# merge.net
KiCad netlist of a schematic drawn in EAGLE
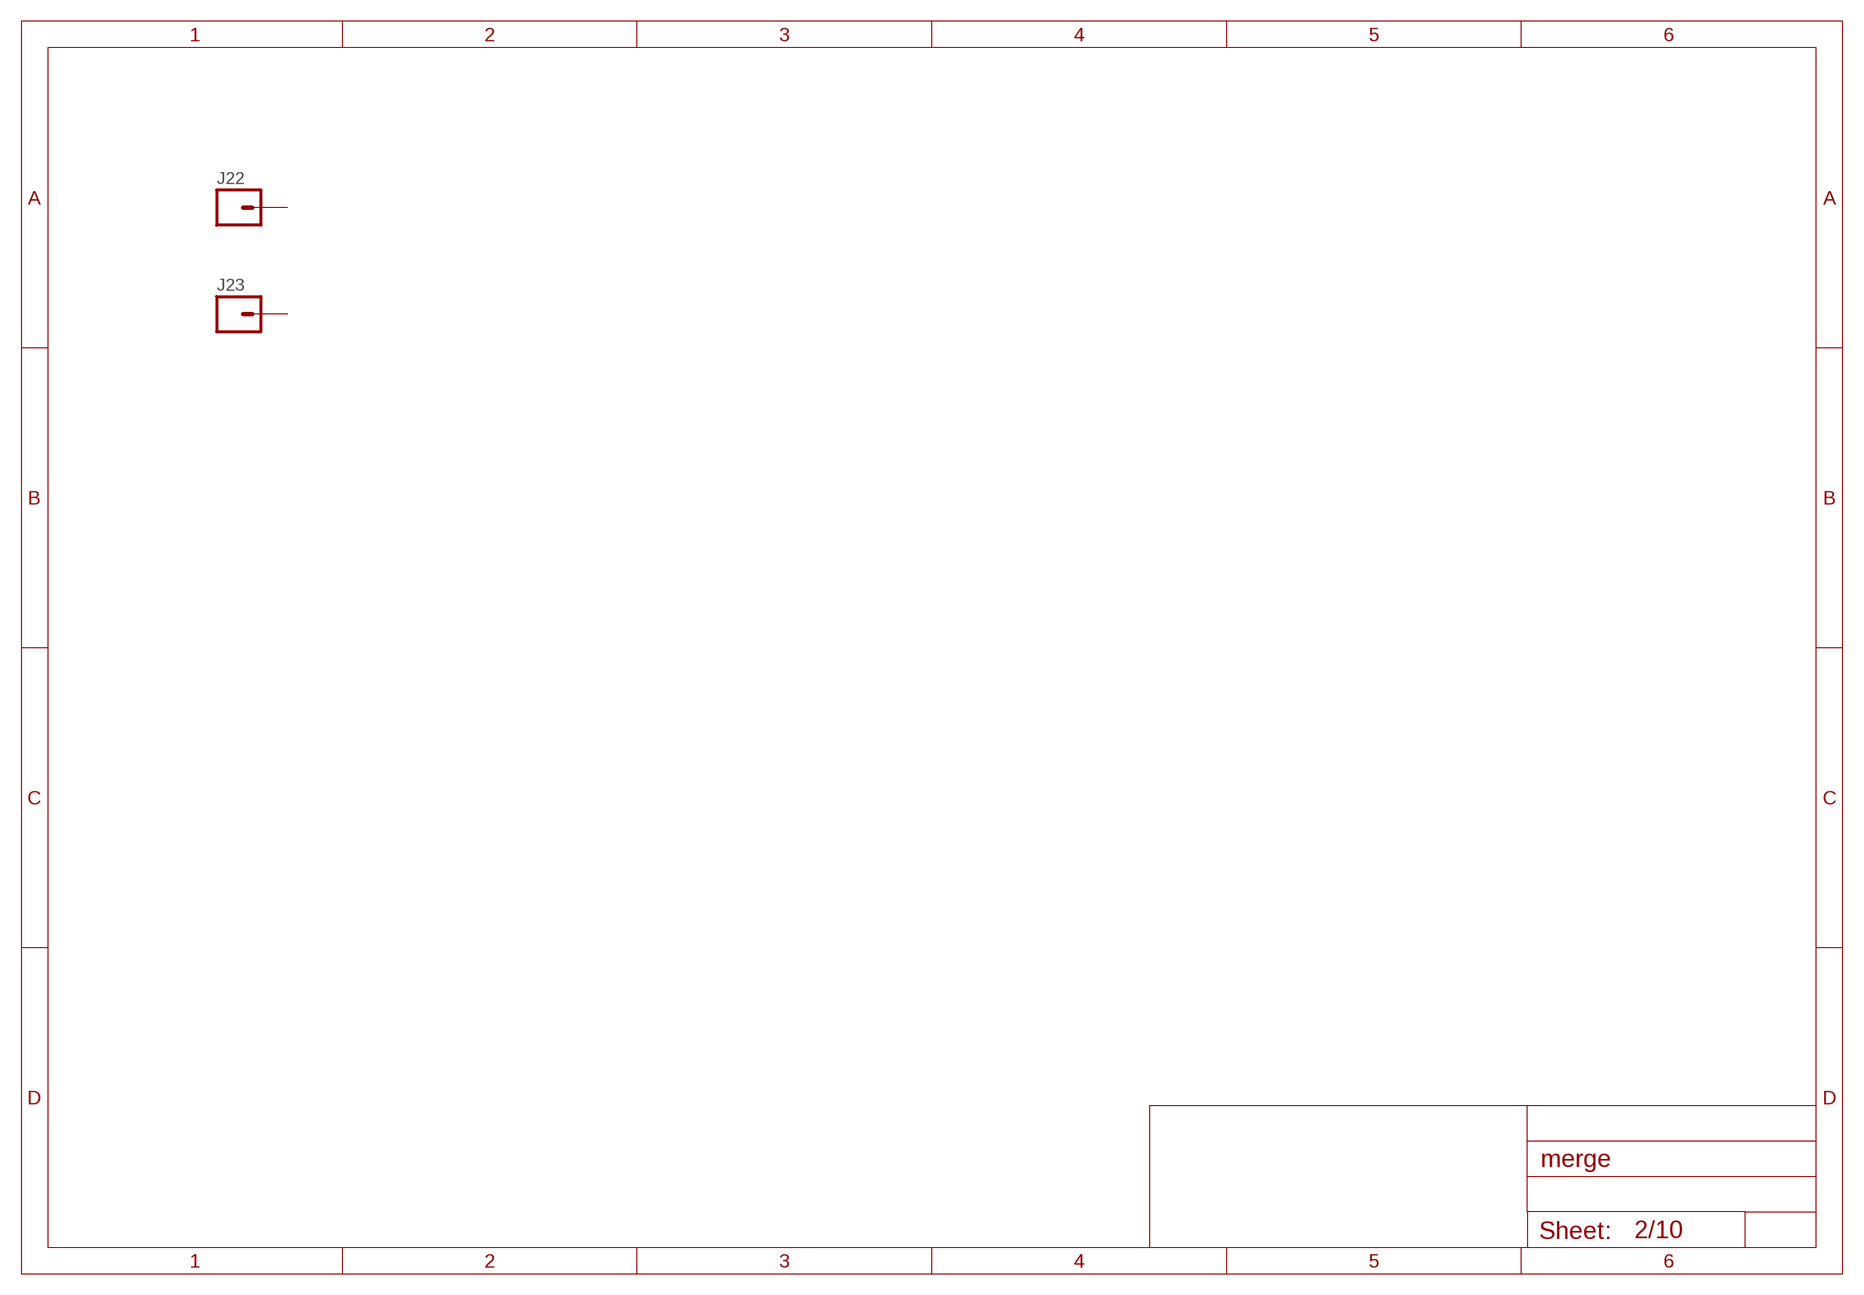
[diagram p0: schematic, sheet 2]
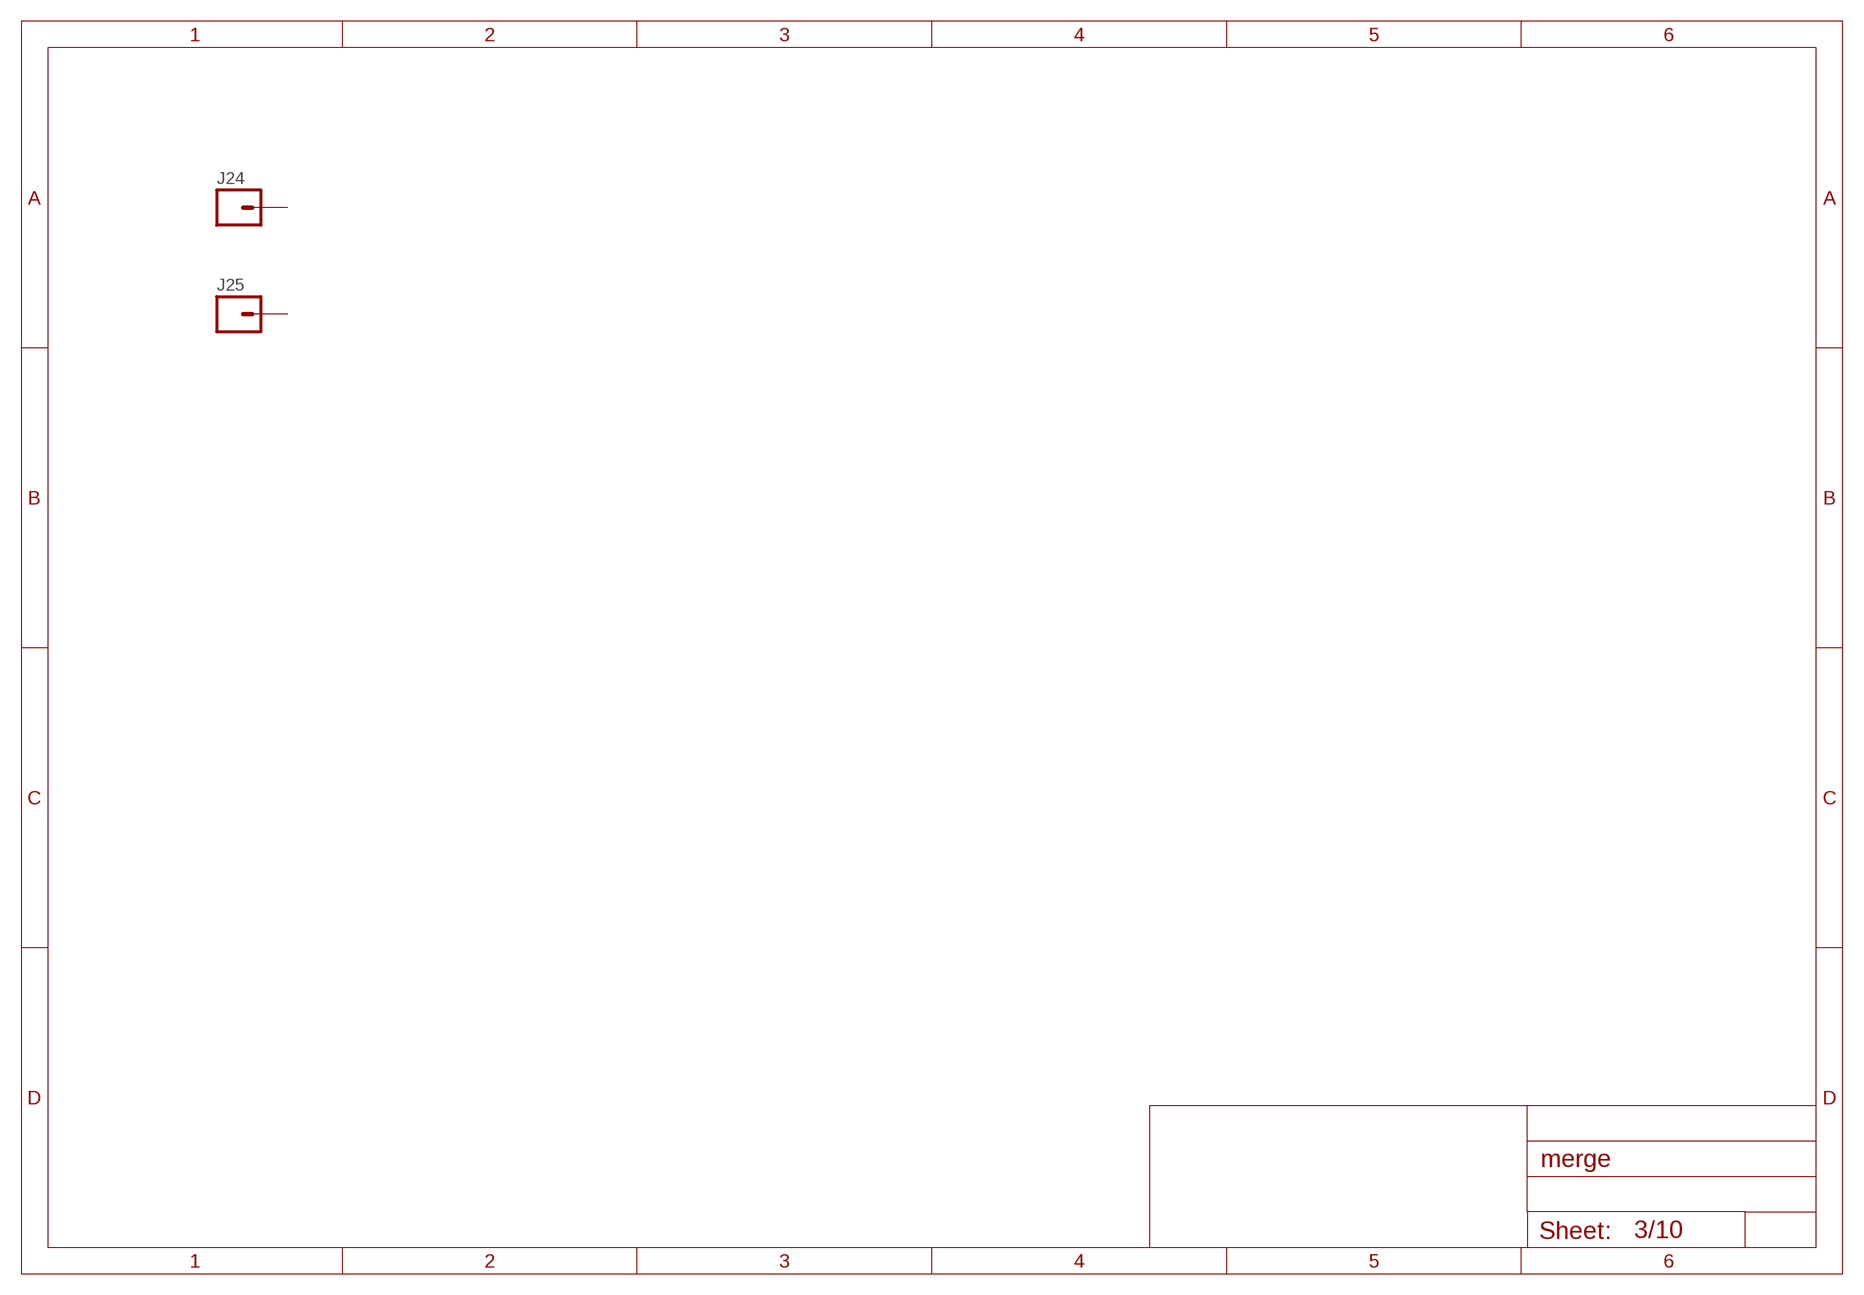
[diagram p1: schematic, sheet 3]
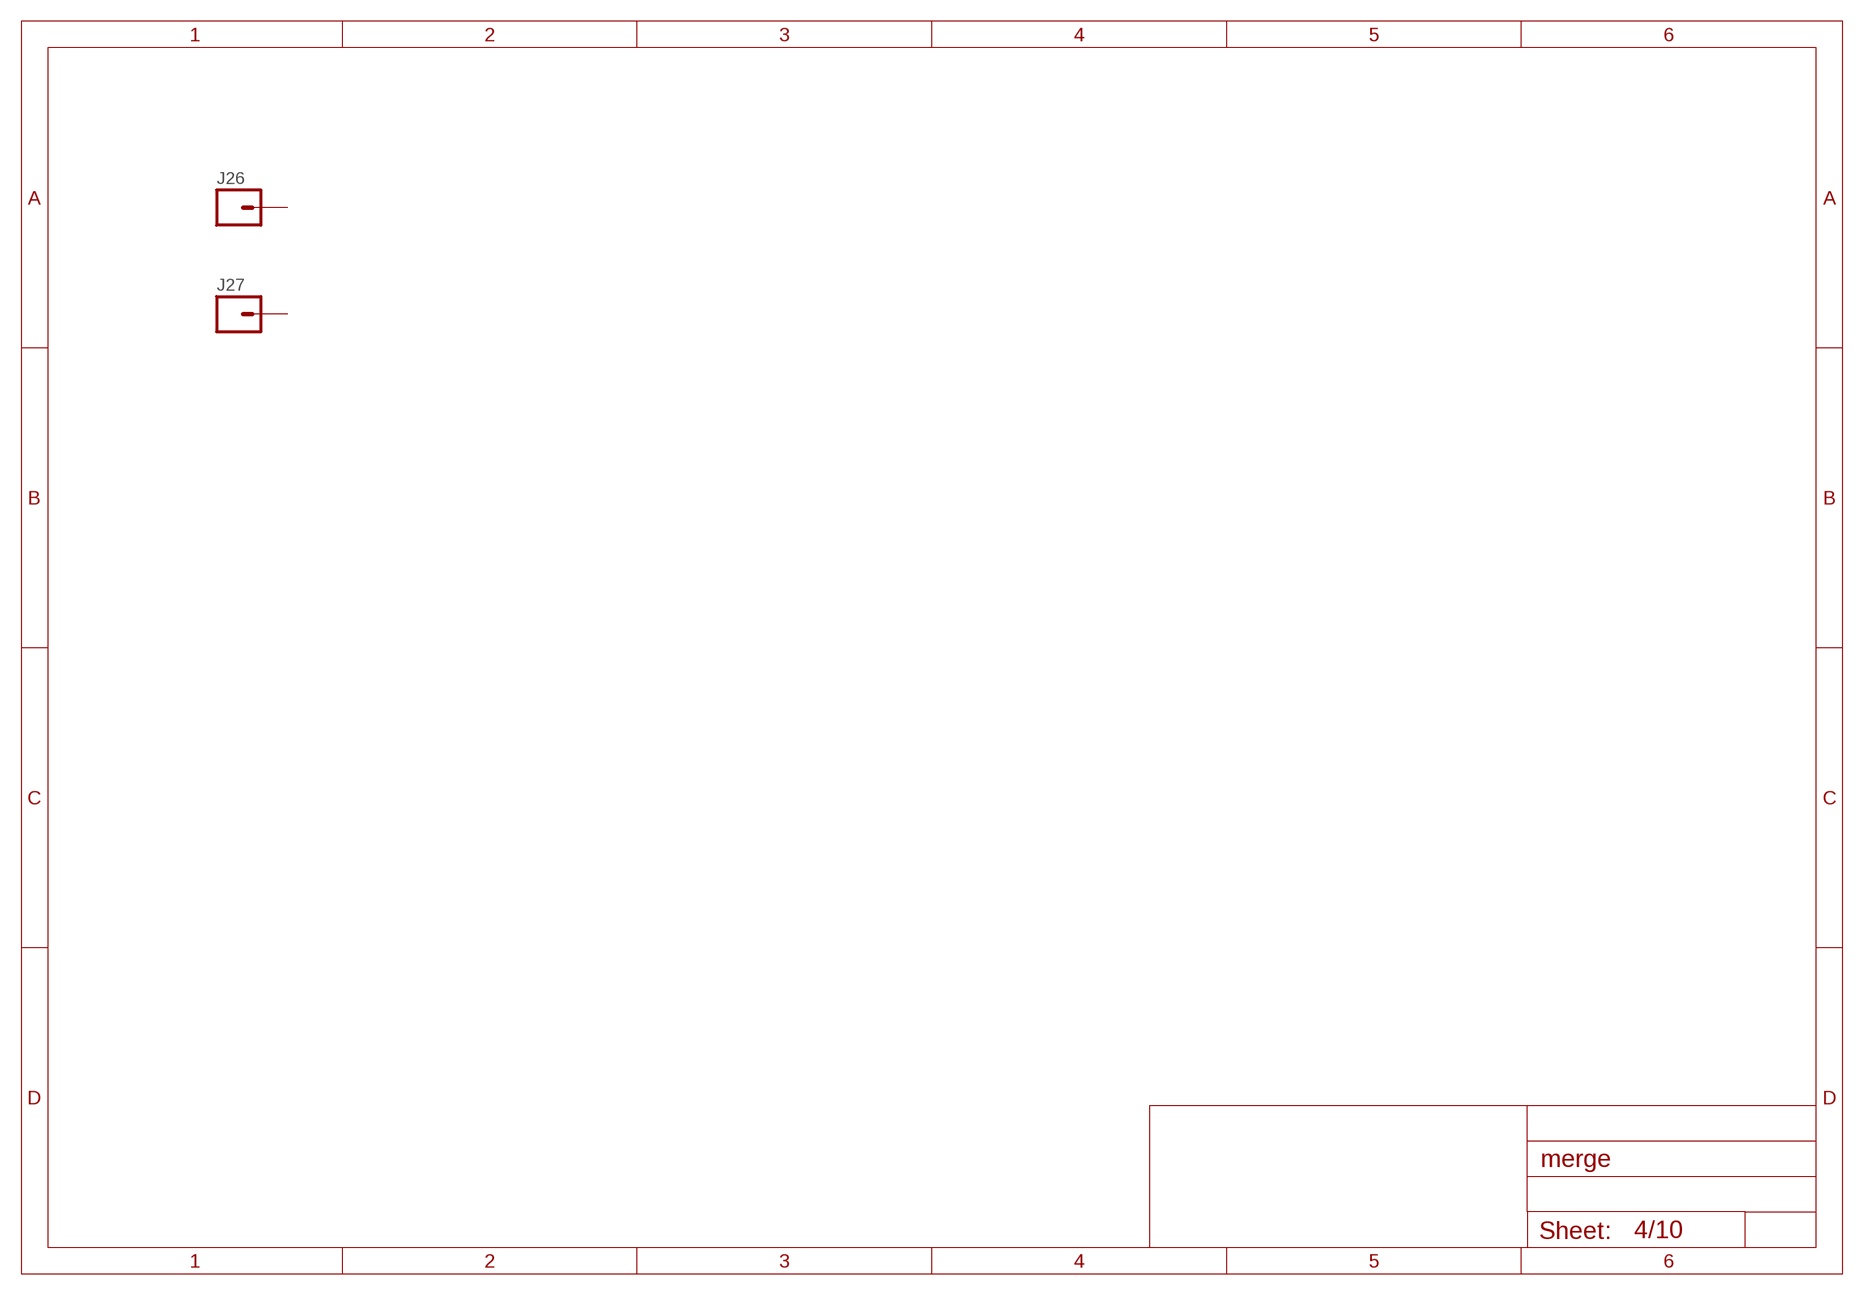
[diagram p2: schematic, sheet 4]
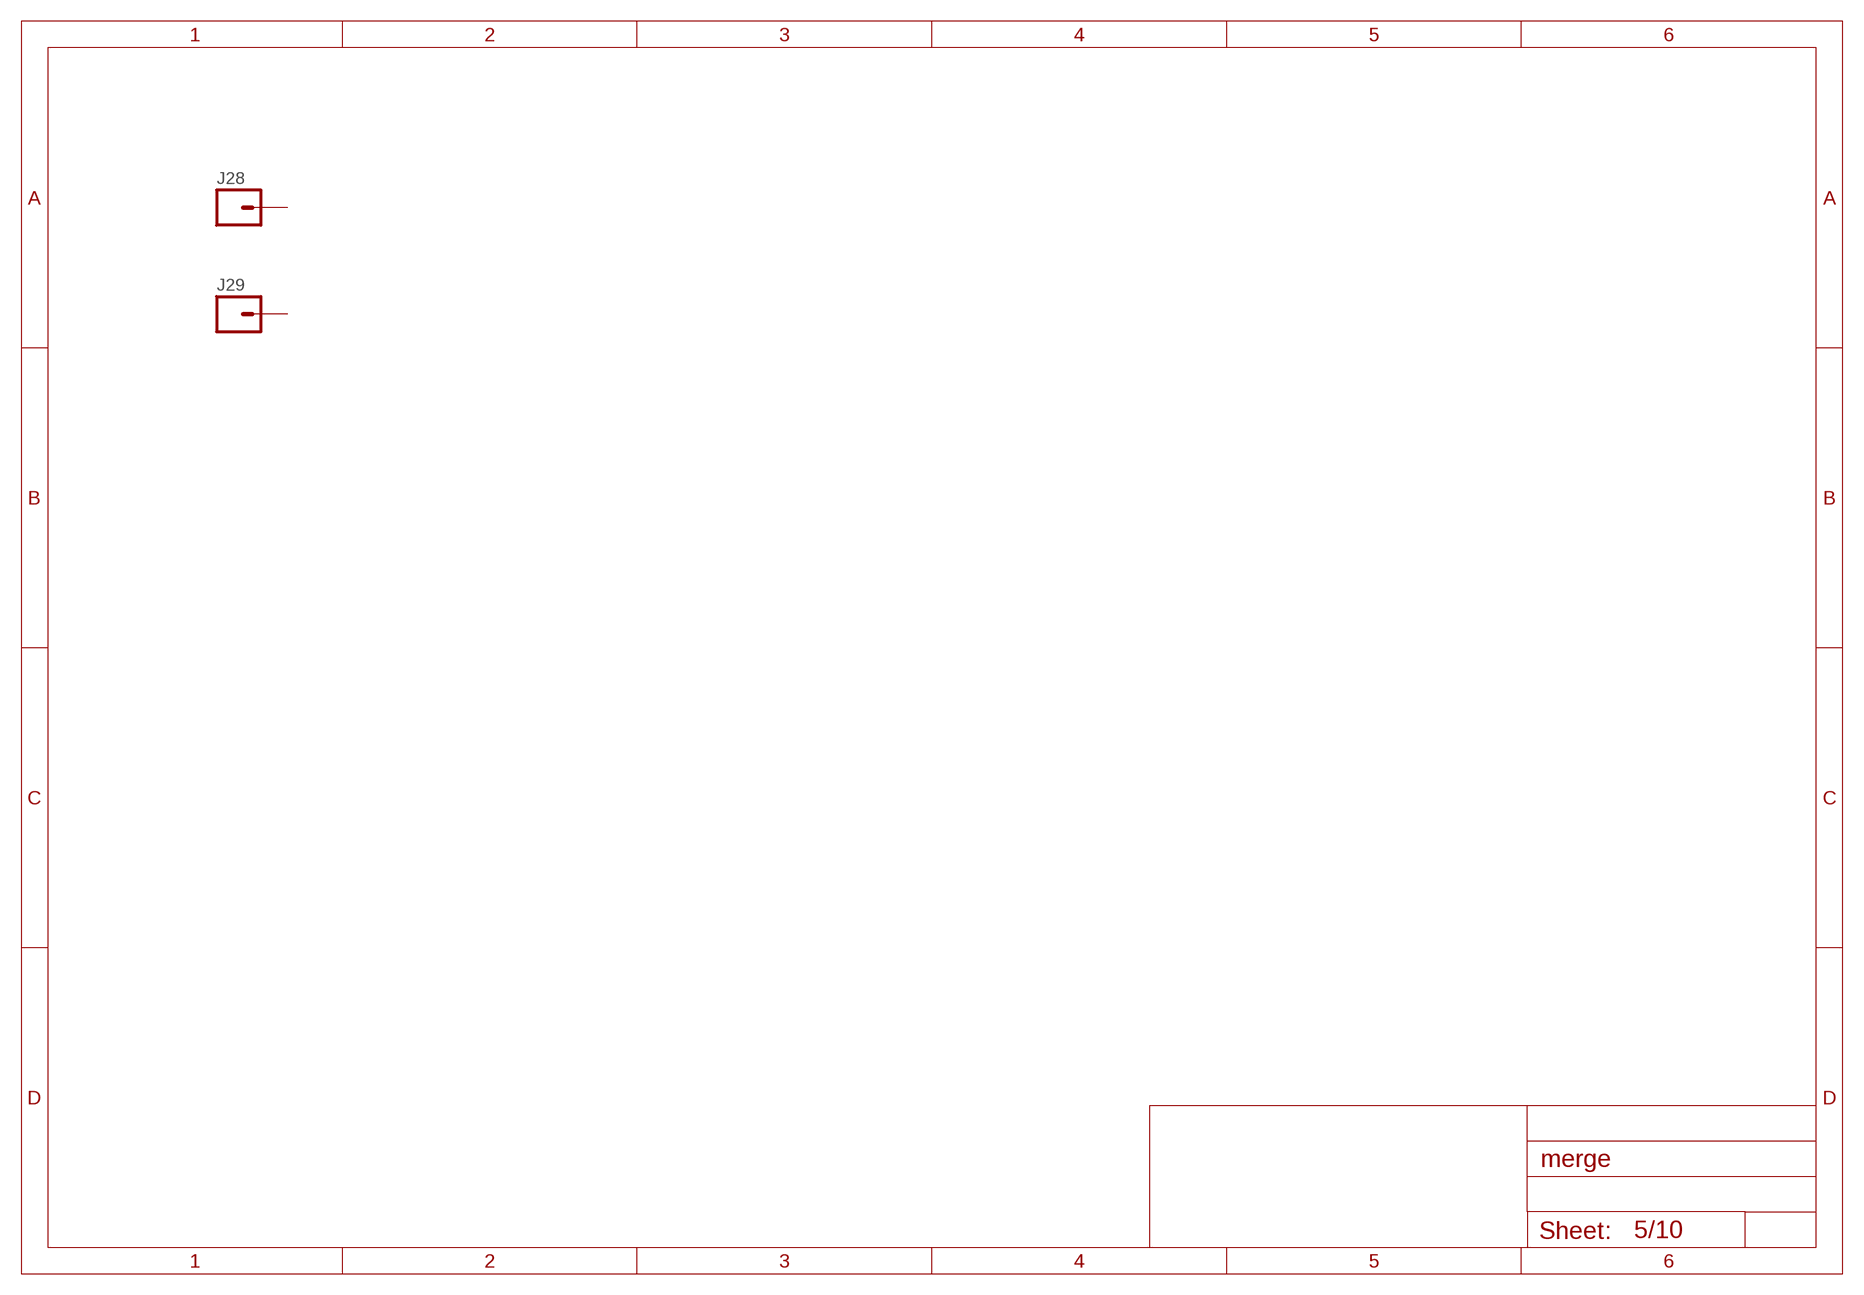
[diagram p3: schematic, sheet 5]
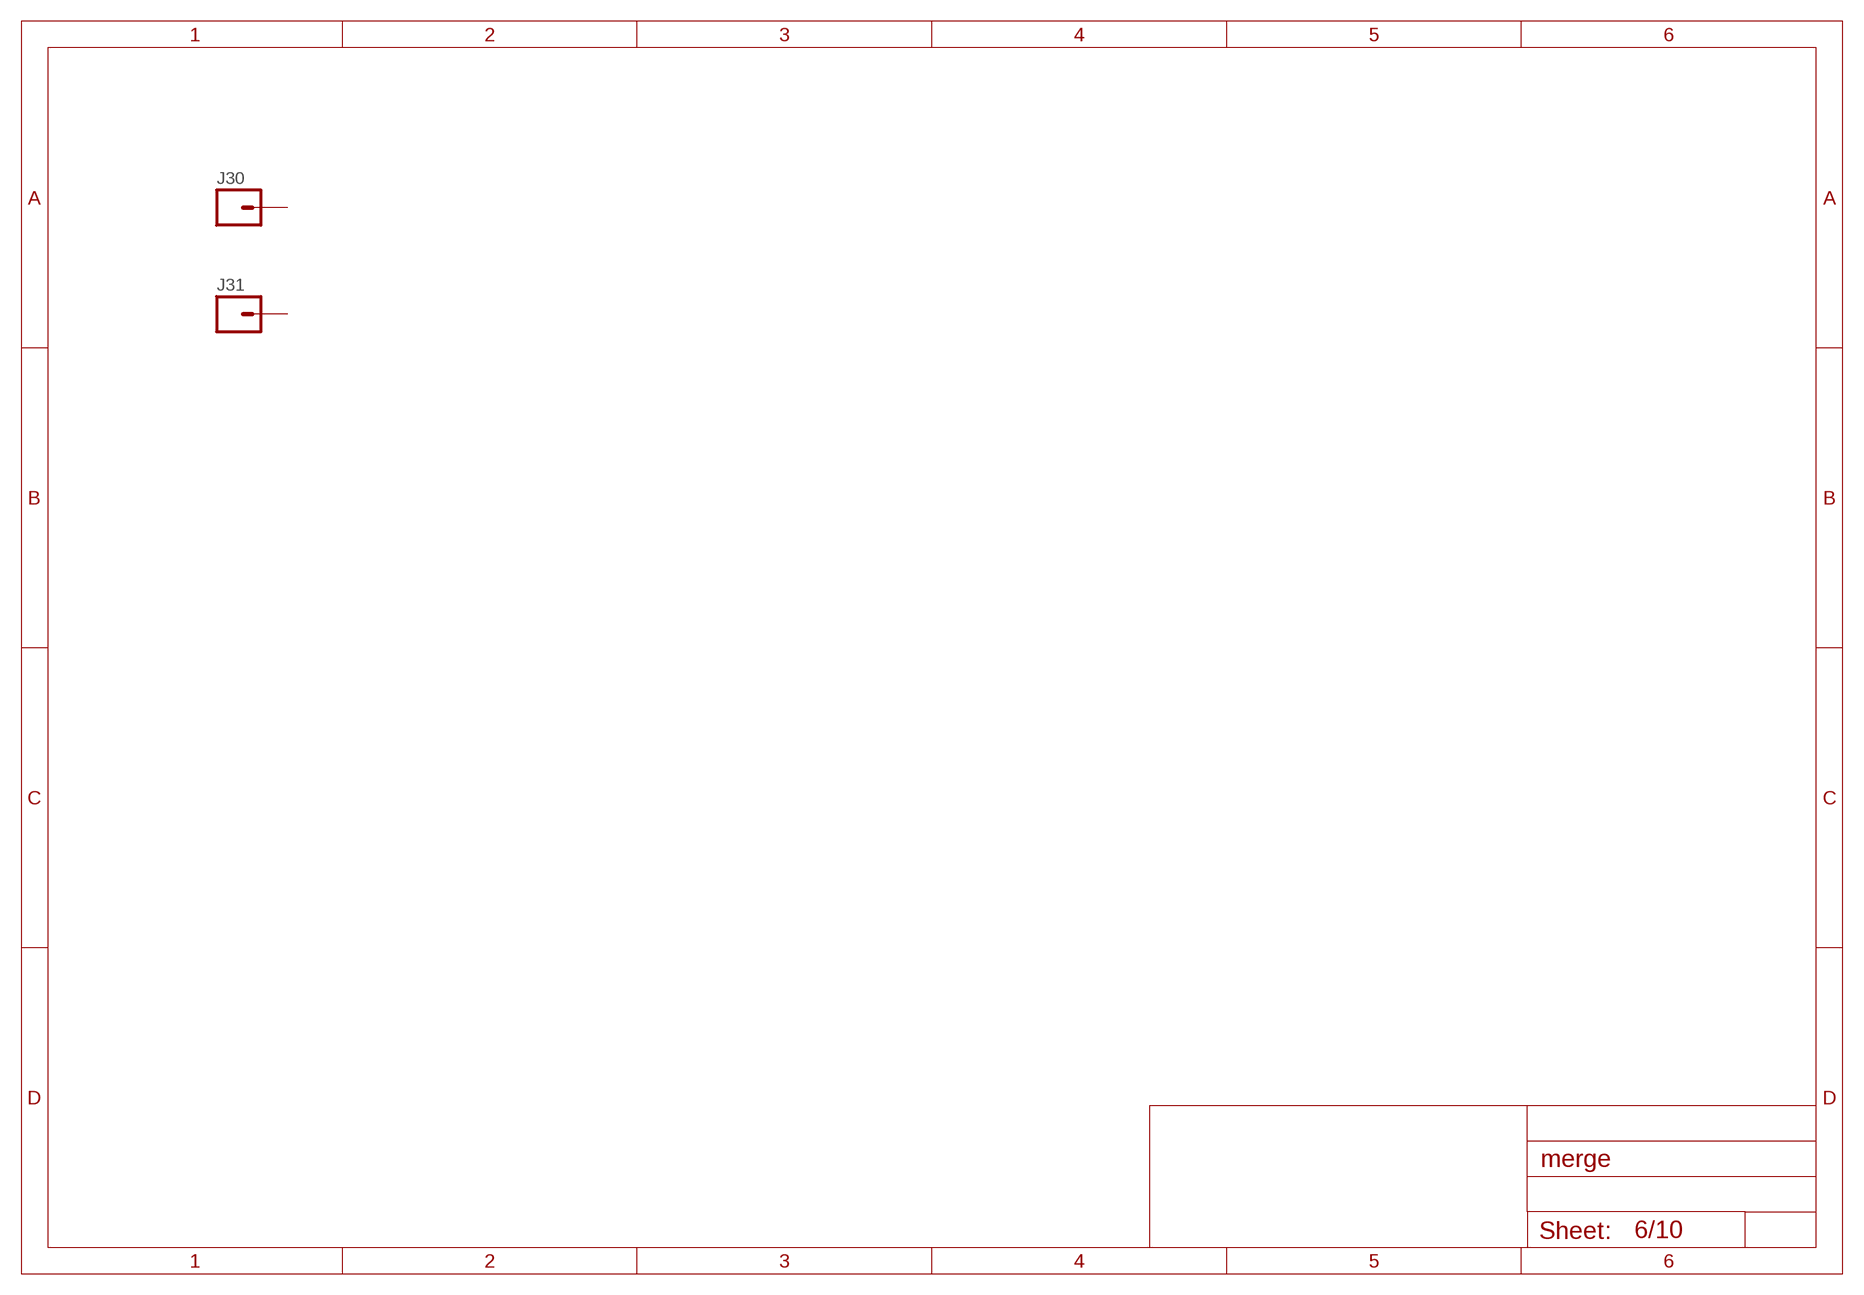
[diagram p4: schematic, sheet 6]
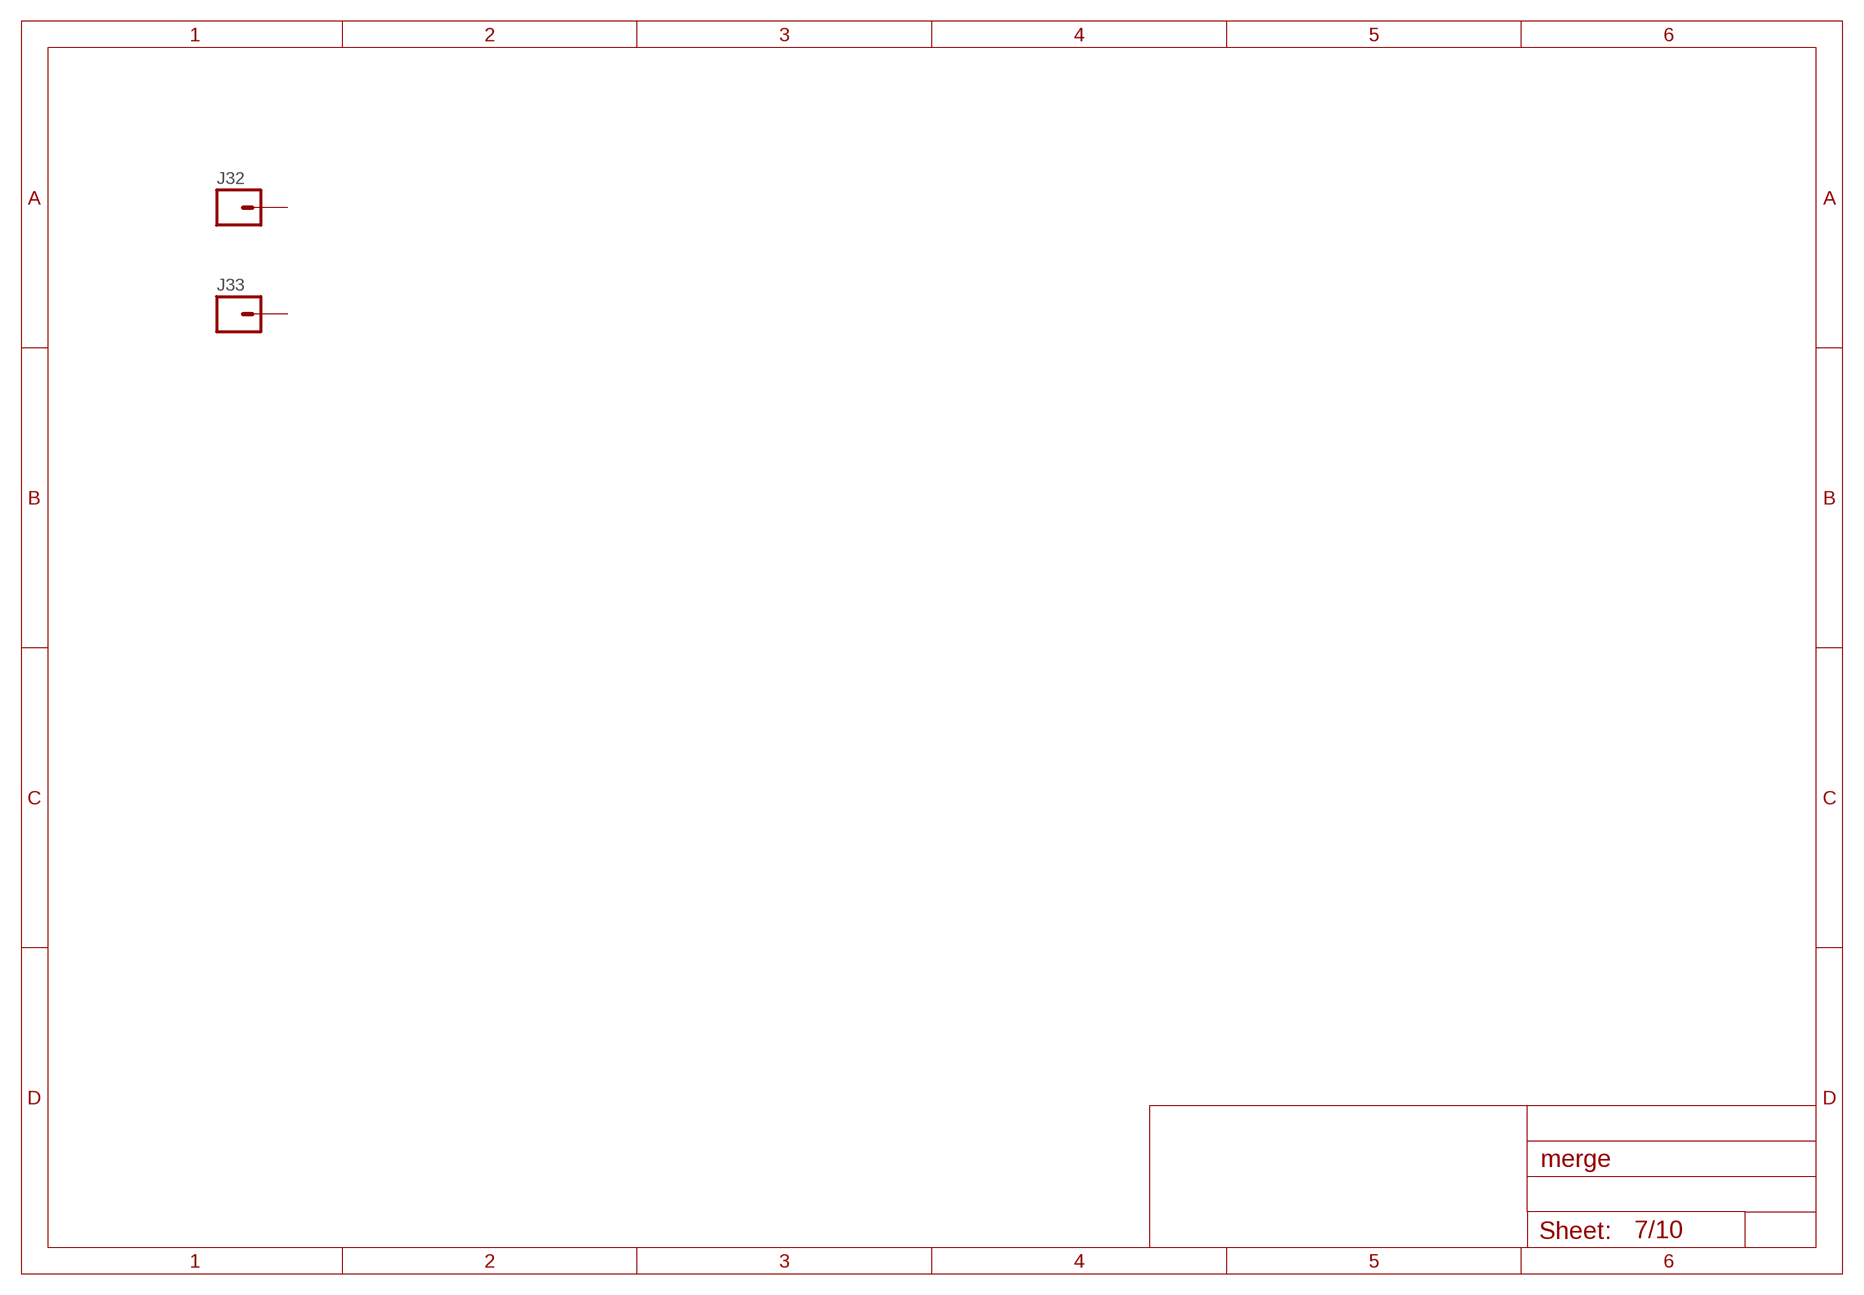
[diagram p5: schematic, sheet 7]
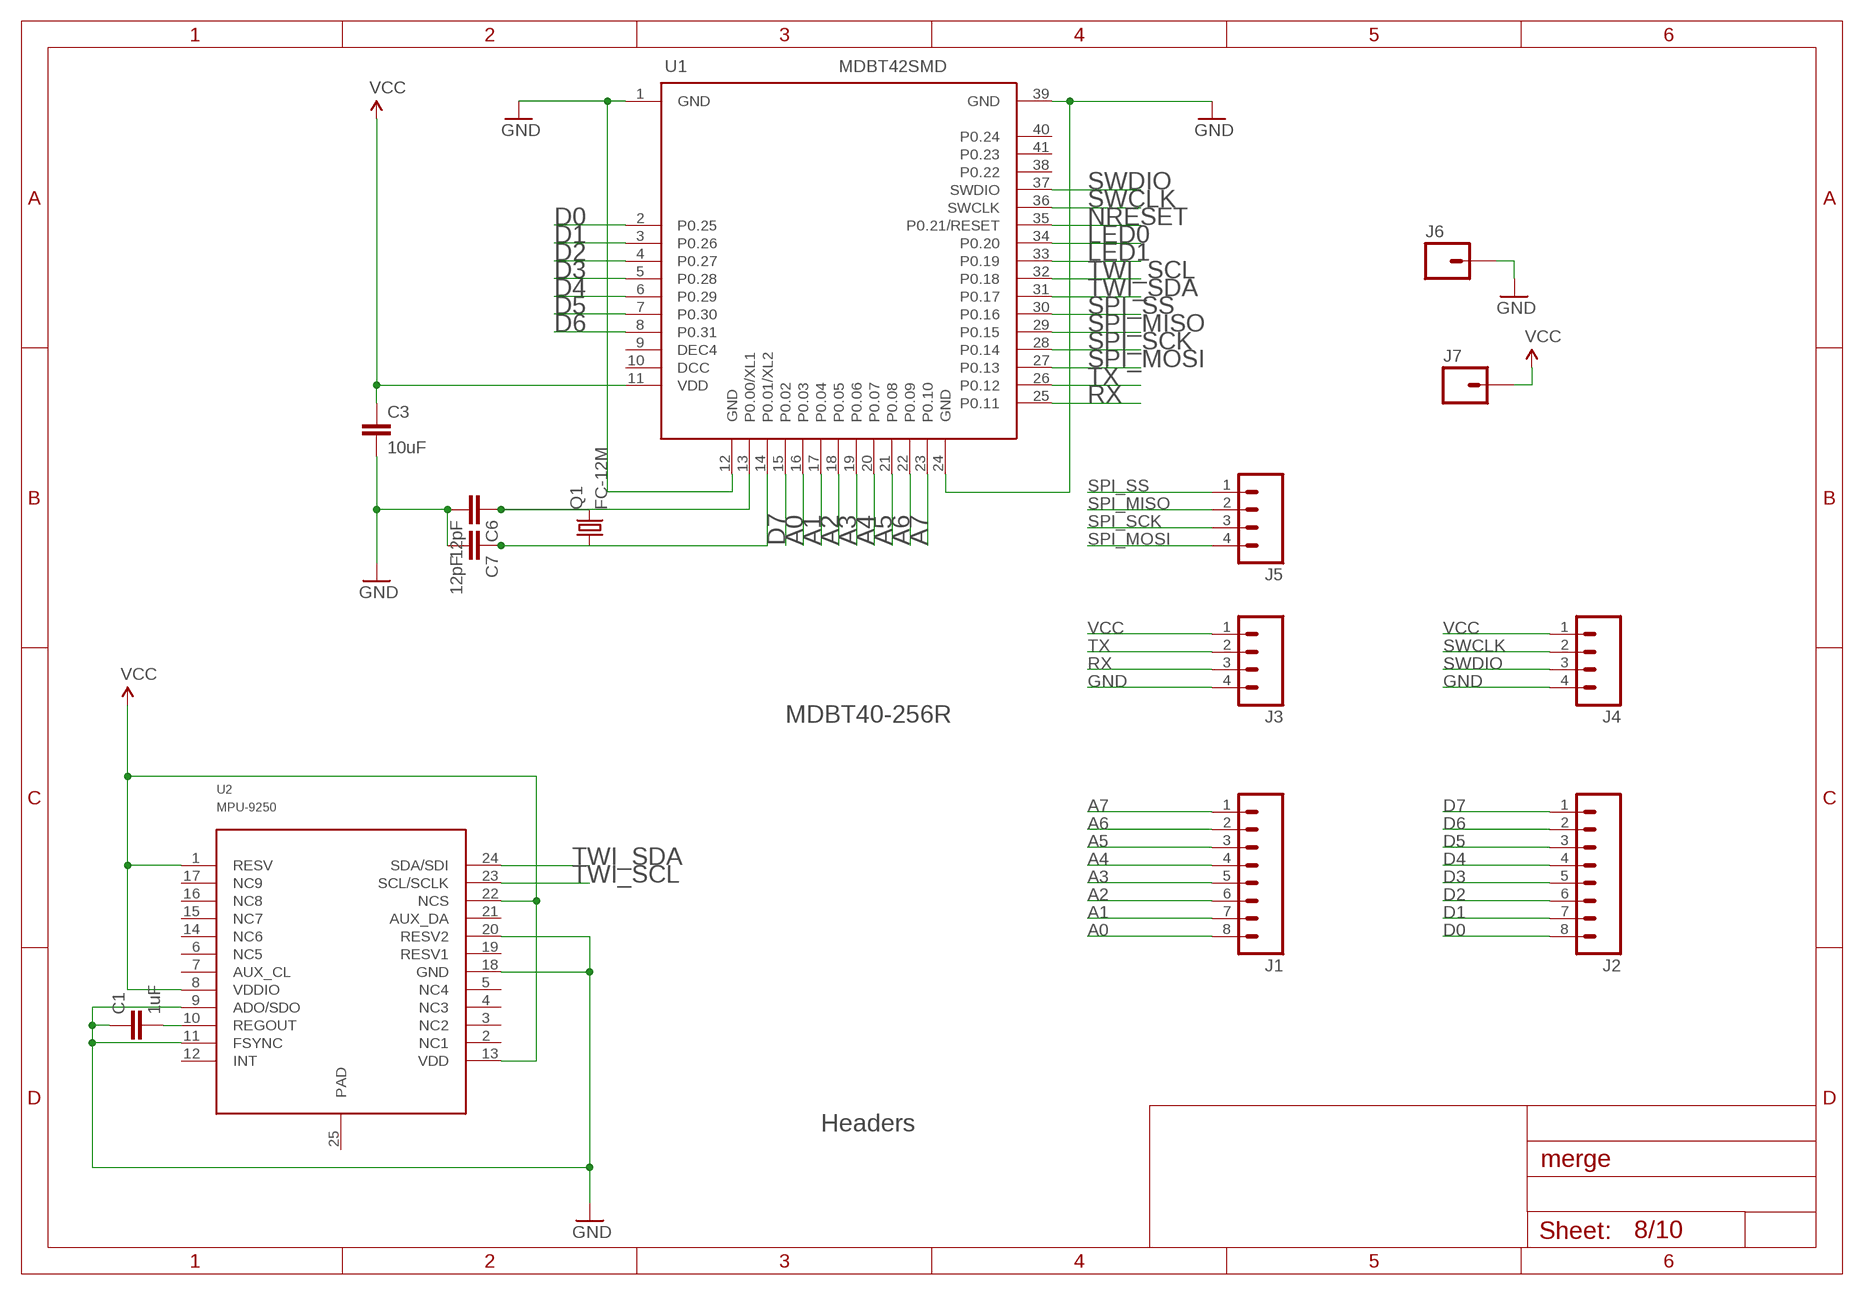
[diagram p6: schematic, sheet 8]
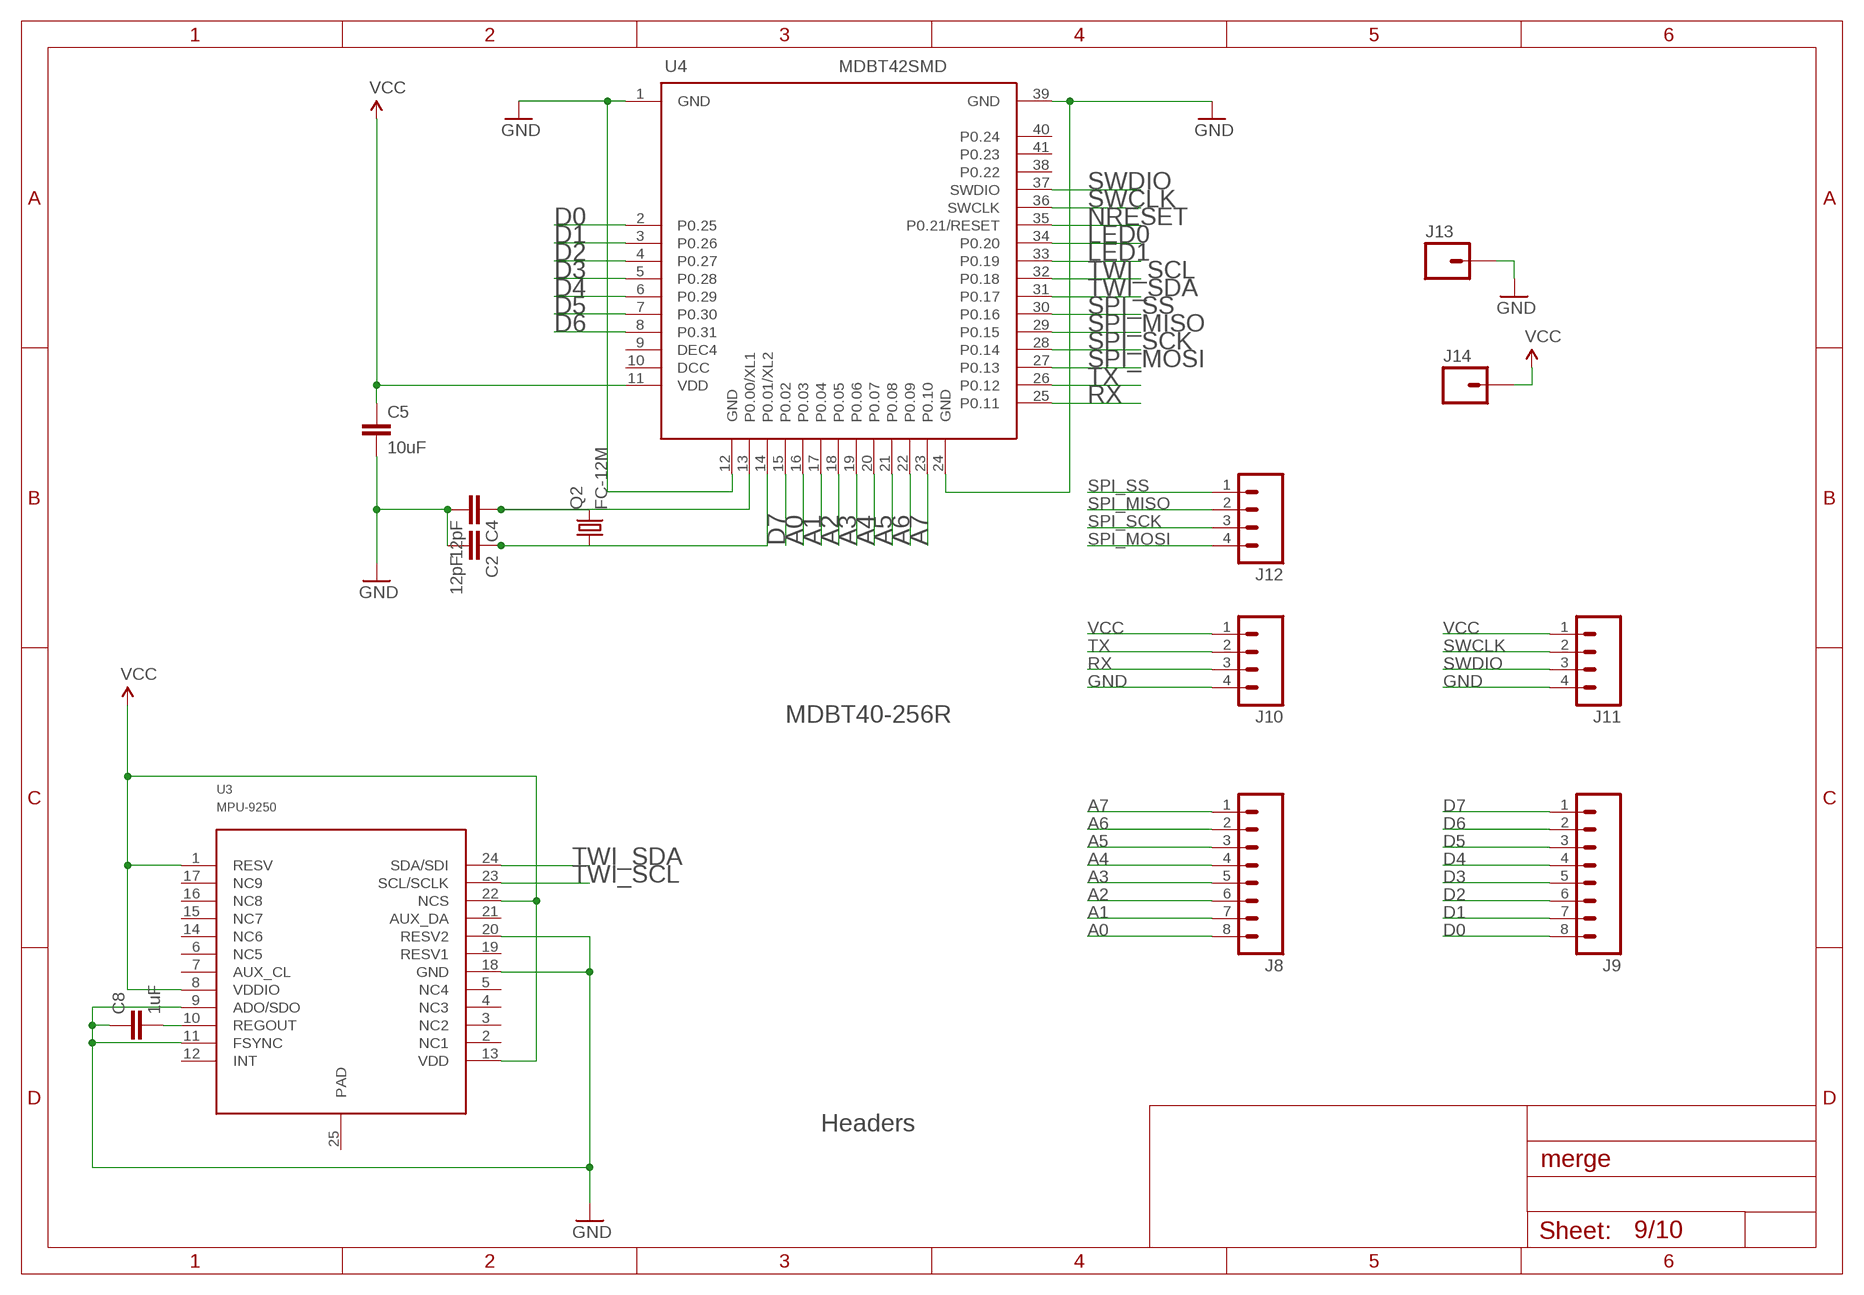
[diagram p7: schematic, sheet 9]
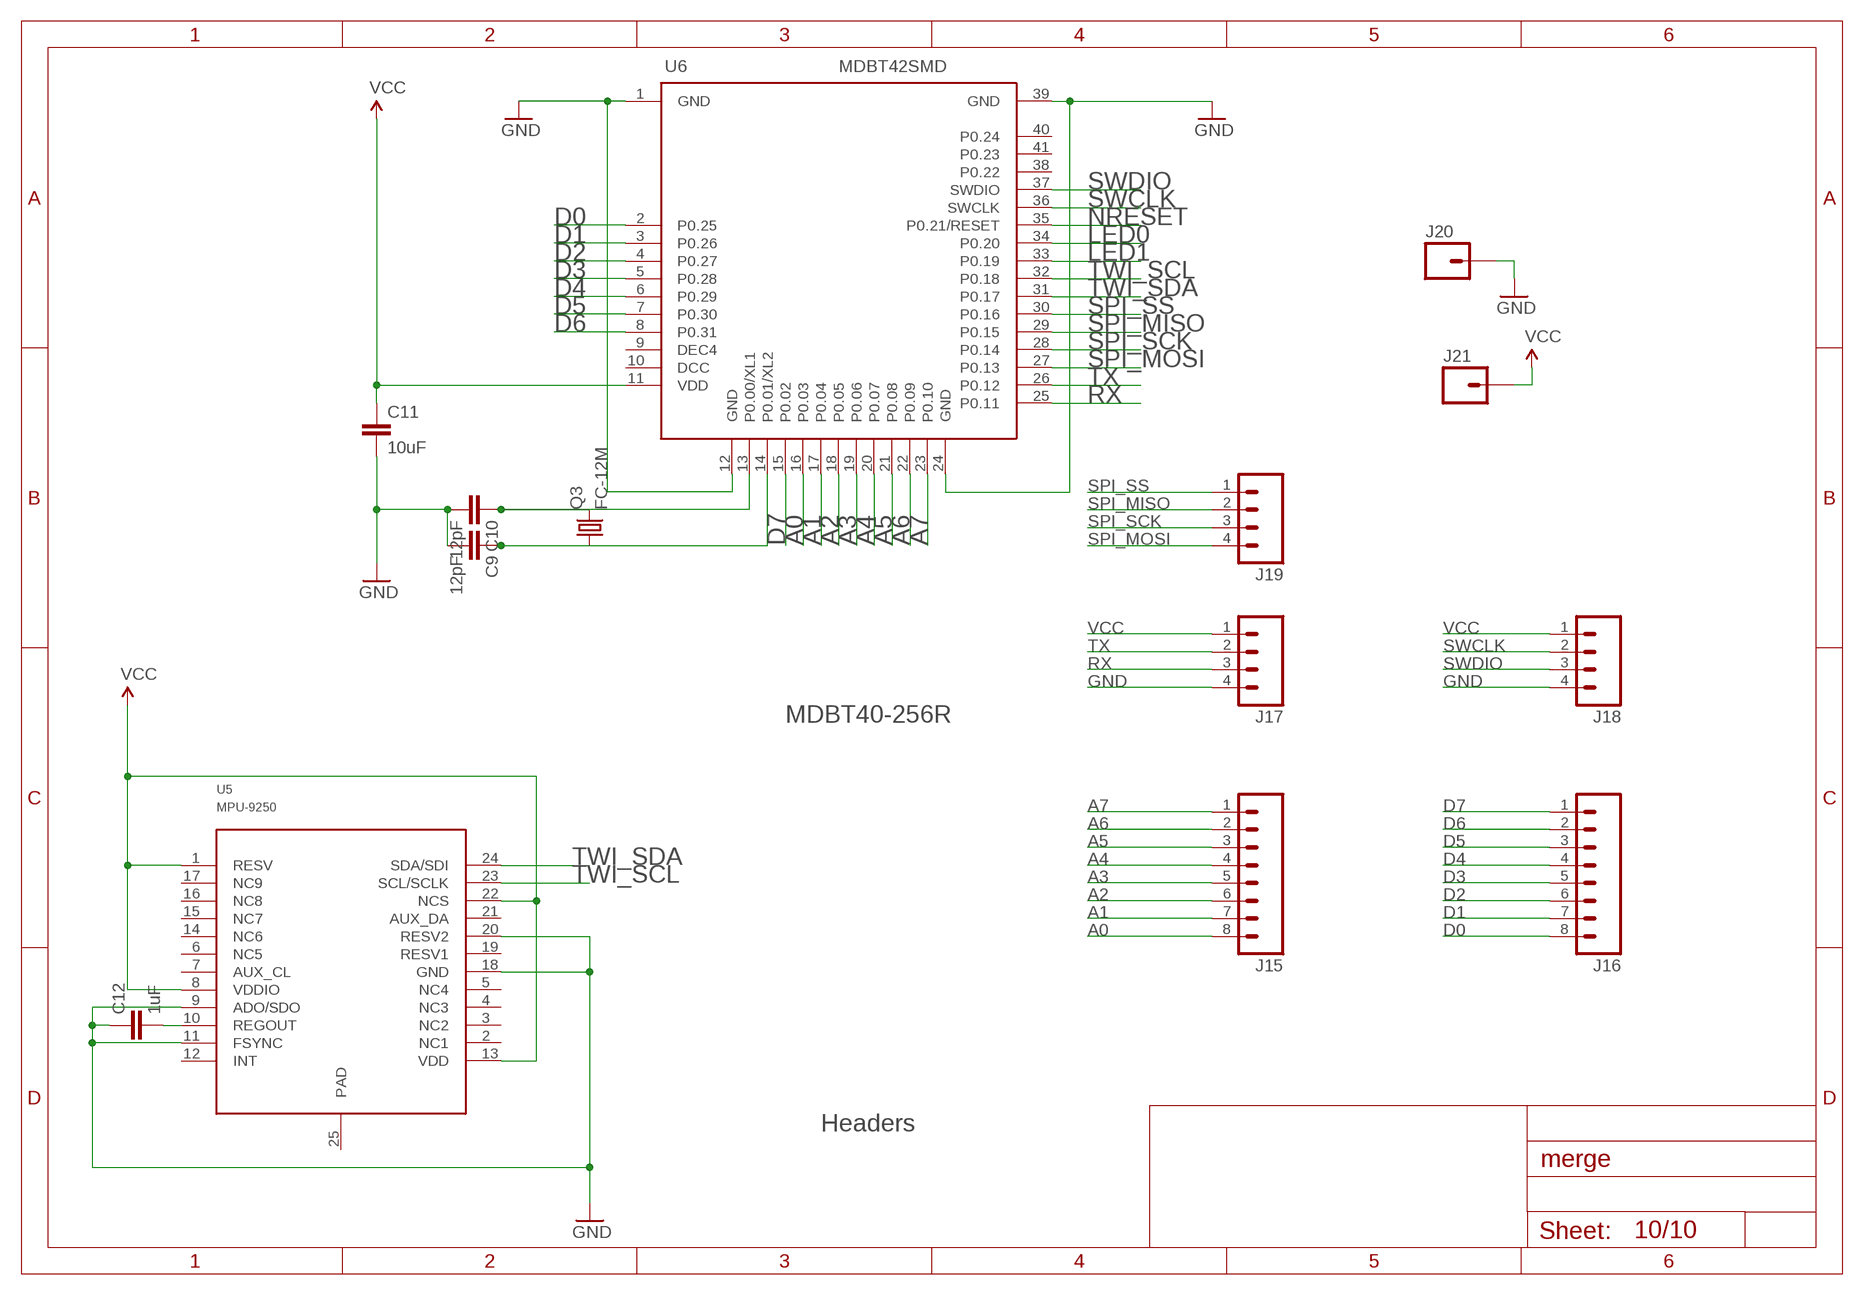
[diagram p8: schematic, sheet 10]

(export (version "E")
  (design (tool "Eeschema 10.0.6"))
  (components
    (comp (ref "C9")
      (value "12pF")
      (footprint "eagle-import:0603-CAP")
      (libsource (lib "eagle-import") (part "CAP0603-CAP"))
    )
    (comp (ref "C10")
      (value "12pF")
      (footprint "eagle-import:0603-CAP")
      (libsource (lib "eagle-import") (part "CAP0603-CAP"))
    )
    (comp (ref "C11")
      (value "10uF")
      (footprint "eagle-import:0603-CAP")
      (libsource (lib "eagle-import") (part "CAP0603-CAP"))
    )
    (comp (ref "C12")
      (value "1uF")
      (footprint "eagle-import:0603-CAP")
      (libsource (lib "eagle-import") (part "CAP0603-CAP"))
    )
    (comp (ref "J15")
      (value "M08SILK_FEMALE_PTH")
      (footprint "eagle-import:1X08")
      (libsource (lib "eagle-import") (part "M08SILK_FEMALE_PTH"))
    )
    (comp (ref "J16")
      (value "M08SILK_FEMALE_PTH")
      (footprint "eagle-import:1X08")
      (libsource (lib "eagle-import") (part "M08SILK_FEMALE_PTH"))
    )
    (comp (ref "J17")
      (value "M04PTH")
      (footprint "eagle-import:1X04")
      (libsource (lib "eagle-import") (part "M04PTH"))
    )
    (comp (ref "J18")
      (value "M04PTH")
      (footprint "eagle-import:1X04")
      (libsource (lib "eagle-import") (part "M04PTH"))
    )
    (comp (ref "J19")
      (value "M04PTH")
      (footprint "eagle-import:1X04")
      (libsource (lib "eagle-import") (part "M04PTH"))
    )
    (comp (ref "J20")
      (value "M01_SMDSMD_4X2")
      (footprint "eagle-import:1X01_SMD")
      (libsource (lib "eagle-import") (part "M01_SMDSMD_4X2"))
    )
    (comp (ref "J21")
      (value "M01_SMDSMD_4X2")
      (footprint "eagle-import:1X01_SMD")
      (libsource (lib "eagle-import") (part "M01_SMDSMD_4X2"))
    )
    (comp (ref "Q3")
      (value "FC-12M")
      (footprint "eagle-import:FC-12M")
      (libsource (lib "eagle-import") (part "FC-12M"))
    )
    (comp (ref "U5")
      (value "MPU-9250")
      (footprint "eagle-import:LEAD-QFN24")
      (libsource (lib "eagle-import") (part "MPU-9250"))
    )
    (comp (ref "U6")
      (value "MDBT42SMD")
      (footprint "eagle-import:MDBT42")
      (libsource (lib "eagle-import") (part "MDBT42SMD"))
    )
    (comp (ref "C1")
      (value "1uF")
      (footprint "eagle-import:0603-CAP")
      (libsource (lib "eagle-import") (part "CAP0603-CAP"))
    )
    (comp (ref "C3")
      (value "10uF")
      (footprint "eagle-import:0603-CAP")
      (libsource (lib "eagle-import") (part "CAP0603-CAP"))
    )
    (comp (ref "C6")
      (value "12pF")
      (footprint "eagle-import:0603-CAP")
      (libsource (lib "eagle-import") (part "CAP0603-CAP"))
    )
    (comp (ref "C7")
      (value "12pF")
      (footprint "eagle-import:0603-CAP")
      (libsource (lib "eagle-import") (part "CAP0603-CAP"))
    )
    (comp (ref "J1")
      (value "M08SILK_FEMALE_PTH")
      (footprint "eagle-import:1X08")
      (libsource (lib "eagle-import") (part "M08SILK_FEMALE_PTH"))
    )
    (comp (ref "J2")
      (value "M08SILK_FEMALE_PTH")
      (footprint "eagle-import:1X08")
      (libsource (lib "eagle-import") (part "M08SILK_FEMALE_PTH"))
    )
    (comp (ref "J3")
      (value "M04PTH")
      (footprint "eagle-import:1X04")
      (libsource (lib "eagle-import") (part "M04PTH"))
    )
    (comp (ref "J4")
      (value "M04PTH")
      (footprint "eagle-import:1X04")
      (libsource (lib "eagle-import") (part "M04PTH"))
    )
    (comp (ref "J5")
      (value "M04PTH")
      (footprint "eagle-import:1X04")
      (libsource (lib "eagle-import") (part "M04PTH"))
    )
    (comp (ref "J6")
      (value "M01_SMDSMD_4X2")
      (footprint "eagle-import:1X01_SMD")
      (libsource (lib "eagle-import") (part "M01_SMDSMD_4X2"))
    )
    (comp (ref "J7")
      (value "M01_SMDSMD_4X2")
      (footprint "eagle-import:1X01_SMD")
      (libsource (lib "eagle-import") (part "M01_SMDSMD_4X2"))
    )
    (comp (ref "Q1")
      (value "FC-12M")
      (footprint "eagle-import:FC-12M")
      (libsource (lib "eagle-import") (part "FC-12M"))
    )
    (comp (ref "U1")
      (value "MDBT42SMD")
      (footprint "eagle-import:MDBT42")
      (libsource (lib "eagle-import") (part "MDBT42SMD"))
    )
    (comp (ref "U2")
      (value "MPU-9250")
      (footprint "eagle-import:LEAD-QFN24")
      (libsource (lib "eagle-import") (part "MPU-9250"))
    )
    (comp (ref "J30")
      (value "M01")
      (footprint "eagle-import:1X01_BIG")
      (libsource (lib "eagle-import") (part "M01"))
    )
    (comp (ref "J31")
      (value "M01")
      (footprint "eagle-import:1X01_BIG")
      (libsource (lib "eagle-import") (part "M01"))
    )
    (comp (ref "J22")
      (value "M01")
      (footprint "eagle-import:1X01_BIG")
      (libsource (lib "eagle-import") (part "M01"))
    )
    (comp (ref "J23")
      (value "M01")
      (footprint "eagle-import:1X01_BIG")
      (libsource (lib "eagle-import") (part "M01"))
    )
    (comp (ref "C2")
      (value "12pF")
      (footprint "eagle-import:0603-CAP")
      (libsource (lib "eagle-import") (part "CAP0603-CAP"))
    )
    (comp (ref "C4")
      (value "12pF")
      (footprint "eagle-import:0603-CAP")
      (libsource (lib "eagle-import") (part "CAP0603-CAP"))
    )
    (comp (ref "C5")
      (value "10uF")
      (footprint "eagle-import:0603-CAP")
      (libsource (lib "eagle-import") (part "CAP0603-CAP"))
    )
    (comp (ref "C8")
      (value "1uF")
      (footprint "eagle-import:0603-CAP")
      (libsource (lib "eagle-import") (part "CAP0603-CAP"))
    )
    (comp (ref "J8")
      (value "M08SILK_FEMALE_PTH")
      (footprint "eagle-import:1X08")
      (libsource (lib "eagle-import") (part "M08SILK_FEMALE_PTH"))
    )
    (comp (ref "J9")
      (value "M08SILK_FEMALE_PTH")
      (footprint "eagle-import:1X08")
      (libsource (lib "eagle-import") (part "M08SILK_FEMALE_PTH"))
    )
    (comp (ref "J10")
      (value "M04PTH")
      (footprint "eagle-import:1X04")
      (libsource (lib "eagle-import") (part "M04PTH"))
    )
    (comp (ref "J11")
      (value "M04PTH")
      (footprint "eagle-import:1X04")
      (libsource (lib "eagle-import") (part "M04PTH"))
    )
    (comp (ref "J12")
      (value "M04PTH")
      (footprint "eagle-import:1X04")
      (libsource (lib "eagle-import") (part "M04PTH"))
    )
    (comp (ref "J13")
      (value "M01_SMDSMD_4X2")
      (footprint "eagle-import:1X01_SMD")
      (libsource (lib "eagle-import") (part "M01_SMDSMD_4X2"))
    )
    (comp (ref "J14")
      (value "M01_SMDSMD_4X2")
      (footprint "eagle-import:1X01_SMD")
      (libsource (lib "eagle-import") (part "M01_SMDSMD_4X2"))
    )
    (comp (ref "Q2")
      (value "FC-12M")
      (footprint "eagle-import:FC-12M")
      (libsource (lib "eagle-import") (part "FC-12M"))
    )
    (comp (ref "U3")
      (value "MPU-9250")
      (footprint "eagle-import:LEAD-QFN24")
      (libsource (lib "eagle-import") (part "MPU-9250"))
    )
    (comp (ref "U4")
      (value "MDBT42SMD")
      (footprint "eagle-import:MDBT42")
      (libsource (lib "eagle-import") (part "MDBT42SMD"))
    )
    (comp (ref "J32")
      (value "M01")
      (footprint "eagle-import:1X01_BIG")
      (libsource (lib "eagle-import") (part "M01"))
    )
    (comp (ref "J33")
      (value "M01")
      (footprint "eagle-import:1X01_BIG")
      (libsource (lib "eagle-import") (part "M01"))
    )
    (comp (ref "J28")
      (value "M01")
      (footprint "eagle-import:1X01_BIG")
      (libsource (lib "eagle-import") (part "M01"))
    )
    (comp (ref "J29")
      (value "M01")
      (footprint "eagle-import:1X01_BIG")
      (libsource (lib "eagle-import") (part "M01"))
    )
    (comp (ref "J24")
      (value "M01")
      (footprint "eagle-import:1X01_BIG")
      (libsource (lib "eagle-import") (part "M01"))
    )
    (comp (ref "J25")
      (value "M01")
      (footprint "eagle-import:1X01_BIG")
      (libsource (lib "eagle-import") (part "M01"))
    )
    (comp (ref "J26")
      (value "M01")
      (footprint "eagle-import:1X01_BIG")
      (libsource (lib "eagle-import") (part "M01"))
    )
    (comp (ref "J27")
      (value "M01")
      (footprint "eagle-import:1X01_BIG")
      (libsource (lib "eagle-import") (part "M01"))
    )
  )
  (nets
    (net (code "1") (name "A0") (class "Default")
      (node (ref "J1") (pin "8") (pinfunction "8_8") (pintype "passive"))
      (node (ref "J15") (pin "8") (pinfunction "8_8") (pintype "passive"))
      (node (ref "J8") (pin "8") (pinfunction "8_8") (pintype "passive"))
      (node (ref "U1") (pin "16") (pinfunction "P0.03_16") (pintype "bidirectional"))
      (node (ref "U4") (pin "16") (pinfunction "P0.03_16") (pintype "bidirectional"))
      (node (ref "U6") (pin "16") (pinfunction "P0.03_16") (pintype "bidirectional"))
    )
    (net (code "2") (name "A1") (class "Default")
      (node (ref "J1") (pin "7") (pinfunction "7_7") (pintype "passive"))
      (node (ref "J15") (pin "7") (pinfunction "7_7") (pintype "passive"))
      (node (ref "J8") (pin "7") (pinfunction "7_7") (pintype "passive"))
      (node (ref "U1") (pin "17") (pinfunction "P0.04_17") (pintype "bidirectional"))
      (node (ref "U4") (pin "17") (pinfunction "P0.04_17") (pintype "bidirectional"))
      (node (ref "U6") (pin "17") (pinfunction "P0.04_17") (pintype "bidirectional"))
    )
    (net (code "3") (name "A2") (class "Default")
      (node (ref "J1") (pin "6") (pinfunction "6_6") (pintype "passive"))
      (node (ref "J15") (pin "6") (pinfunction "6_6") (pintype "passive"))
      (node (ref "J8") (pin "6") (pinfunction "6_6") (pintype "passive"))
      (node (ref "U1") (pin "18") (pinfunction "P0.05_18") (pintype "bidirectional"))
      (node (ref "U4") (pin "18") (pinfunction "P0.05_18") (pintype "bidirectional"))
      (node (ref "U6") (pin "18") (pinfunction "P0.05_18") (pintype "bidirectional"))
    )
    (net (code "4") (name "A3") (class "Default")
      (node (ref "J1") (pin "5") (pinfunction "5_5") (pintype "passive"))
      (node (ref "J15") (pin "5") (pinfunction "5_5") (pintype "passive"))
      (node (ref "J8") (pin "5") (pinfunction "5_5") (pintype "passive"))
      (node (ref "U1") (pin "19") (pinfunction "P0.06_19") (pintype "bidirectional"))
      (node (ref "U4") (pin "19") (pinfunction "P0.06_19") (pintype "bidirectional"))
      (node (ref "U6") (pin "19") (pinfunction "P0.06_19") (pintype "bidirectional"))
    )
    (net (code "5") (name "A4") (class "Default")
      (node (ref "J1") (pin "4") (pinfunction "4_4") (pintype "passive"))
      (node (ref "J15") (pin "4") (pinfunction "4_4") (pintype "passive"))
      (node (ref "J8") (pin "4") (pinfunction "4_4") (pintype "passive"))
      (node (ref "U1") (pin "20") (pinfunction "P0.07_20") (pintype "bidirectional"))
      (node (ref "U4") (pin "20") (pinfunction "P0.07_20") (pintype "bidirectional"))
      (node (ref "U6") (pin "20") (pinfunction "P0.07_20") (pintype "bidirectional"))
    )
    (net (code "6") (name "A5") (class "Default")
      (node (ref "J1") (pin "3") (pinfunction "3_3") (pintype "passive"))
      (node (ref "J15") (pin "3") (pinfunction "3_3") (pintype "passive"))
      (node (ref "J8") (pin "3") (pinfunction "3_3") (pintype "passive"))
      (node (ref "U1") (pin "21") (pinfunction "P0.08_21") (pintype "bidirectional"))
      (node (ref "U4") (pin "21") (pinfunction "P0.08_21") (pintype "bidirectional"))
      (node (ref "U6") (pin "21") (pinfunction "P0.08_21") (pintype "bidirectional"))
    )
    (net (code "7") (name "A6") (class "Default")
      (node (ref "J1") (pin "2") (pinfunction "2_2") (pintype "passive"))
      (node (ref "J15") (pin "2") (pinfunction "2_2") (pintype "passive"))
      (node (ref "J8") (pin "2") (pinfunction "2_2") (pintype "passive"))
      (node (ref "U1") (pin "22") (pinfunction "P0.09_22") (pintype "bidirectional"))
      (node (ref "U4") (pin "22") (pinfunction "P0.09_22") (pintype "bidirectional"))
      (node (ref "U6") (pin "22") (pinfunction "P0.09_22") (pintype "bidirectional"))
    )
    (net (code "8") (name "A7") (class "Default")
      (node (ref "J1") (pin "1") (pinfunction "1_1") (pintype "passive"))
      (node (ref "J15") (pin "1") (pinfunction "1_1") (pintype "passive"))
      (node (ref "J8") (pin "1") (pinfunction "1_1") (pintype "passive"))
      (node (ref "U1") (pin "23") (pinfunction "P0.10_23") (pintype "bidirectional"))
      (node (ref "U4") (pin "23") (pinfunction "P0.10_23") (pintype "bidirectional"))
      (node (ref "U6") (pin "23") (pinfunction "P0.10_23") (pintype "bidirectional"))
    )
    (net (code "9") (name "D0") (class "Default")
      (node (ref "J16") (pin "8") (pinfunction "8_8") (pintype "passive"))
      (node (ref "J2") (pin "8") (pinfunction "8_8") (pintype "passive"))
      (node (ref "J9") (pin "8") (pinfunction "8_8") (pintype "passive"))
      (node (ref "U1") (pin "2") (pinfunction "P0.25_2") (pintype "bidirectional"))
      (node (ref "U4") (pin "2") (pinfunction "P0.25_2") (pintype "bidirectional"))
      (node (ref "U6") (pin "2") (pinfunction "P0.25_2") (pintype "bidirectional"))
    )
    (net (code "10") (name "D1") (class "Default")
      (node (ref "J16") (pin "7") (pinfunction "7_7") (pintype "passive"))
      (node (ref "J2") (pin "7") (pinfunction "7_7") (pintype "passive"))
      (node (ref "J9") (pin "7") (pinfunction "7_7") (pintype "passive"))
      (node (ref "U1") (pin "3") (pinfunction "P0.26_3") (pintype "bidirectional"))
      (node (ref "U4") (pin "3") (pinfunction "P0.26_3") (pintype "bidirectional"))
      (node (ref "U6") (pin "3") (pinfunction "P0.26_3") (pintype "bidirectional"))
    )
    (net (code "11") (name "D2") (class "Default")
      (node (ref "J16") (pin "6") (pinfunction "6_6") (pintype "passive"))
      (node (ref "J2") (pin "6") (pinfunction "6_6") (pintype "passive"))
      (node (ref "J9") (pin "6") (pinfunction "6_6") (pintype "passive"))
      (node (ref "U1") (pin "4") (pinfunction "P0.27_4") (pintype "bidirectional"))
      (node (ref "U4") (pin "4") (pinfunction "P0.27_4") (pintype "bidirectional"))
      (node (ref "U6") (pin "4") (pinfunction "P0.27_4") (pintype "bidirectional"))
    )
    (net (code "12") (name "D3") (class "Default")
      (node (ref "J16") (pin "5") (pinfunction "5_5") (pintype "passive"))
      (node (ref "J2") (pin "5") (pinfunction "5_5") (pintype "passive"))
      (node (ref "J9") (pin "5") (pinfunction "5_5") (pintype "passive"))
      (node (ref "U1") (pin "5") (pinfunction "P0.28_5") (pintype "bidirectional"))
      (node (ref "U4") (pin "5") (pinfunction "P0.28_5") (pintype "bidirectional"))
      (node (ref "U6") (pin "5") (pinfunction "P0.28_5") (pintype "bidirectional"))
    )
    (net (code "13") (name "D4") (class "Default")
      (node (ref "J16") (pin "4") (pinfunction "4_4") (pintype "passive"))
      (node (ref "J2") (pin "4") (pinfunction "4_4") (pintype "passive"))
      (node (ref "J9") (pin "4") (pinfunction "4_4") (pintype "passive"))
      (node (ref "U1") (pin "6") (pinfunction "P0.29_6") (pintype "bidirectional"))
      (node (ref "U4") (pin "6") (pinfunction "P0.29_6") (pintype "bidirectional"))
      (node (ref "U6") (pin "6") (pinfunction "P0.29_6") (pintype "bidirectional"))
    )
    (net (code "14") (name "D5") (class "Default")
      (node (ref "J16") (pin "3") (pinfunction "3_3") (pintype "passive"))
      (node (ref "J2") (pin "3") (pinfunction "3_3") (pintype "passive"))
      (node (ref "J9") (pin "3") (pinfunction "3_3") (pintype "passive"))
      (node (ref "U1") (pin "7") (pinfunction "P0.30_7") (pintype "bidirectional"))
      (node (ref "U4") (pin "7") (pinfunction "P0.30_7") (pintype "bidirectional"))
      (node (ref "U6") (pin "7") (pinfunction "P0.30_7") (pintype "bidirectional"))
    )
    (net (code "15") (name "D6") (class "Default")
      (node (ref "J16") (pin "2") (pinfunction "2_2") (pintype "passive"))
      (node (ref "J2") (pin "2") (pinfunction "2_2") (pintype "passive"))
      (node (ref "J9") (pin "2") (pinfunction "2_2") (pintype "passive"))
      (node (ref "U1") (pin "8") (pinfunction "P0.31_8") (pintype "bidirectional"))
      (node (ref "U4") (pin "8") (pinfunction "P0.31_8") (pintype "bidirectional"))
      (node (ref "U6") (pin "8") (pinfunction "P0.31_8") (pintype "bidirectional"))
    )
    (net (code "16") (name "D7") (class "Default")
      (node (ref "J16") (pin "1") (pinfunction "1_1") (pintype "passive"))
      (node (ref "J2") (pin "1") (pinfunction "1_1") (pintype "passive"))
      (node (ref "J9") (pin "1") (pinfunction "1_1") (pintype "passive"))
      (node (ref "U1") (pin "15") (pinfunction "P0.02_15") (pintype "bidirectional"))
      (node (ref "U4") (pin "15") (pinfunction "P0.02_15") (pintype "bidirectional"))
      (node (ref "U6") (pin "15") (pinfunction "P0.02_15") (pintype "bidirectional"))
    )
    (net (code "17") (name "GND") (class "Default")
      (node (ref "C1") (pin "1") (pinfunction "1_1") (pintype "passive"))
      (node (ref "C10") (pin "2") (pinfunction "2_2") (pintype "passive"))
      (node (ref "C11") (pin "2") (pinfunction "2_2") (pintype "passive"))
      (node (ref "C12") (pin "1") (pinfunction "1_1") (pintype "passive"))
      (node (ref "C2") (pin "2") (pinfunction "2_2") (pintype "passive"))
      (node (ref "C3") (pin "2") (pinfunction "2_2") (pintype "passive"))
      (node (ref "C4") (pin "2") (pinfunction "2_2") (pintype "passive"))
      (node (ref "C5") (pin "2") (pinfunction "2_2") (pintype "passive"))
      (node (ref "C6") (pin "2") (pinfunction "2_2") (pintype "passive"))
      (node (ref "C7") (pin "2") (pinfunction "2_2") (pintype "passive"))
      (node (ref "C8") (pin "1") (pinfunction "1_1") (pintype "passive"))
      (node (ref "C9") (pin "2") (pinfunction "2_2") (pintype "passive"))
      (node (ref "J10") (pin "4") (pinfunction "4_4") (pintype "passive"))
      (node (ref "J11") (pin "4") (pinfunction "4_4") (pintype "passive"))
      (node (ref "J13") (pin "P$1") (pinfunction "1_P$1") (pintype "passive"))
      (node (ref "J17") (pin "4") (pinfunction "4_4") (pintype "passive"))
      (node (ref "J18") (pin "4") (pinfunction "4_4") (pintype "passive"))
      (node (ref "J20") (pin "P$1") (pinfunction "1_P$1") (pintype "passive"))
      (node (ref "J3") (pin "4") (pinfunction "4_4") (pintype "passive"))
      (node (ref "J4") (pin "4") (pinfunction "4_4") (pintype "passive"))
      (node (ref "J6") (pin "P$1") (pinfunction "1_P$1") (pintype "passive"))
      (node (ref "U1") (pin "1") (pinfunction "GND_1") (pintype "bidirectional"))
      (node (ref "U1") (pin "12") (pinfunction "GND_12") (pintype "bidirectional"))
      (node (ref "U1") (pin "24") (pinfunction "GND_24") (pintype "bidirectional"))
      (node (ref "U1") (pin "39") (pinfunction "GND_39") (pintype "bidirectional"))
      (node (ref "U2") (pin "11") (pinfunction "FSYNC_11") (pintype "bidirectional"))
      (node (ref "U2") (pin "18") (pinfunction "GND_18") (pintype "bidirectional"))
      (node (ref "U2") (pin "20") (pinfunction "RESV2_20") (pintype "bidirectional"))
      (node (ref "U2") (pin "9") (pinfunction "ADO/SDO_9") (pintype "bidirectional"))
      (node (ref "U3") (pin "11") (pinfunction "FSYNC_11") (pintype "bidirectional"))
      (node (ref "U3") (pin "18") (pinfunction "GND_18") (pintype "bidirectional"))
      (node (ref "U3") (pin "20") (pinfunction "RESV2_20") (pintype "bidirectional"))
      (node (ref "U3") (pin "9") (pinfunction "ADO/SDO_9") (pintype "bidirectional"))
      (node (ref "U4") (pin "1") (pinfunction "GND_1") (pintype "bidirectional"))
      (node (ref "U4") (pin "12") (pinfunction "GND_12") (pintype "bidirectional"))
      (node (ref "U4") (pin "24") (pinfunction "GND_24") (pintype "bidirectional"))
      (node (ref "U4") (pin "39") (pinfunction "GND_39") (pintype "bidirectional"))
      (node (ref "U5") (pin "11") (pinfunction "FSYNC_11") (pintype "bidirectional"))
      (node (ref "U5") (pin "18") (pinfunction "GND_18") (pintype "bidirectional"))
      (node (ref "U5") (pin "20") (pinfunction "RESV2_20") (pintype "bidirectional"))
      (node (ref "U5") (pin "9") (pinfunction "ADO/SDO_9") (pintype "bidirectional"))
      (node (ref "U6") (pin "1") (pinfunction "GND_1") (pintype "bidirectional"))
      (node (ref "U6") (pin "12") (pinfunction "GND_12") (pintype "bidirectional"))
      (node (ref "U6") (pin "24") (pinfunction "GND_24") (pintype "bidirectional"))
      (node (ref "U6") (pin "39") (pinfunction "GND_39") (pintype "bidirectional"))
    )
    (net (code "18") (name "LED0") (class "Default")
      (node (ref "U1") (pin "34") (pinfunction "P0.20_34") (pintype "bidirectional"))
      (node (ref "U4") (pin "34") (pinfunction "P0.20_34") (pintype "bidirectional"))
      (node (ref "U6") (pin "34") (pinfunction "P0.20_34") (pintype "bidirectional"))
    )
    (net (code "19") (name "LED1") (class "Default")
      (node (ref "U1") (pin "33") (pinfunction "P0.19_33") (pintype "bidirectional"))
      (node (ref "U4") (pin "33") (pinfunction "P0.19_33") (pintype "bidirectional"))
      (node (ref "U6") (pin "33") (pinfunction "P0.19_33") (pintype "bidirectional"))
    )
    (net (code "20") (name "NRESET") (class "Default")
      (node (ref "U1") (pin "35") (pinfunction "P0.21/RESET_35") (pintype "bidirectional"))
      (node (ref "U4") (pin "35") (pinfunction "P0.21/RESET_35") (pintype "bidirectional"))
      (node (ref "U6") (pin "35") (pinfunction "P0.21/RESET_35") (pintype "bidirectional"))
    )
    (net (code "21") (name "Net-(U1-P0.00{slash}XL1)") (class "Default")
      (node (ref "C6") (pin "1") (pinfunction "1_1") (pintype "passive"))
      (node (ref "Q1") (pin "2") (pinfunction "2_2") (pintype "passive"))
      (node (ref "U1") (pin "13") (pinfunction "P0.00/XL1_13") (pintype "bidirectional"))
    )
    (net (code "22") (name "Net-(U1-P0.01{slash}XL2)") (class "Default")
      (node (ref "C7") (pin "1") (pinfunction "1_1") (pintype "passive"))
      (node (ref "Q1") (pin "1") (pinfunction "1_1") (pintype "passive"))
      (node (ref "U1") (pin "14") (pinfunction "P0.01/XL2_14") (pintype "bidirectional"))
    )
    (net (code "23") (name "Net-(U2-REGOUT)") (class "Default")
      (node (ref "C1") (pin "2") (pinfunction "2_2") (pintype "passive"))
      (node (ref "U2") (pin "10") (pinfunction "REGOUT_10") (pintype "bidirectional"))
    )
    (net (code "24") (name "Net-(U3-REGOUT)") (class "Default")
      (node (ref "C8") (pin "2") (pinfunction "2_2") (pintype "passive"))
      (node (ref "U3") (pin "10") (pinfunction "REGOUT_10") (pintype "bidirectional"))
    )
    (net (code "25") (name "Net-(U4-P0.00{slash}XL1)") (class "Default")
      (node (ref "C4") (pin "1") (pinfunction "1_1") (pintype "passive"))
      (node (ref "Q2") (pin "2") (pinfunction "2_2") (pintype "passive"))
      (node (ref "U4") (pin "13") (pinfunction "P0.00/XL1_13") (pintype "bidirectional"))
    )
    (net (code "26") (name "Net-(U4-P0.01{slash}XL2)") (class "Default")
      (node (ref "C2") (pin "1") (pinfunction "1_1") (pintype "passive"))
      (node (ref "Q2") (pin "1") (pinfunction "1_1") (pintype "passive"))
      (node (ref "U4") (pin "14") (pinfunction "P0.01/XL2_14") (pintype "bidirectional"))
    )
    (net (code "27") (name "Net-(U5-REGOUT)") (class "Default")
      (node (ref "C12") (pin "2") (pinfunction "2_2") (pintype "passive"))
      (node (ref "U5") (pin "10") (pinfunction "REGOUT_10") (pintype "bidirectional"))
    )
    (net (code "28") (name "Net-(U6-P0.00{slash}XL1)") (class "Default")
      (node (ref "C10") (pin "1") (pinfunction "1_1") (pintype "passive"))
      (node (ref "Q3") (pin "2") (pinfunction "2_2") (pintype "passive"))
      (node (ref "U6") (pin "13") (pinfunction "P0.00/XL1_13") (pintype "bidirectional"))
    )
    (net (code "29") (name "Net-(U6-P0.01{slash}XL2)") (class "Default")
      (node (ref "C9") (pin "1") (pinfunction "1_1") (pintype "passive"))
      (node (ref "Q3") (pin "1") (pinfunction "1_1") (pintype "passive"))
      (node (ref "U6") (pin "14") (pinfunction "P0.01/XL2_14") (pintype "bidirectional"))
    )
    (net (code "30") (name "RX") (class "Default")
      (node (ref "J10") (pin "3") (pinfunction "3_3") (pintype "passive"))
      (node (ref "J17") (pin "3") (pinfunction "3_3") (pintype "passive"))
      (node (ref "J3") (pin "3") (pinfunction "3_3") (pintype "passive"))
      (node (ref "U1") (pin "25") (pinfunction "P0.11_25") (pintype "bidirectional"))
      (node (ref "U4") (pin "25") (pinfunction "P0.11_25") (pintype "bidirectional"))
      (node (ref "U6") (pin "25") (pinfunction "P0.11_25") (pintype "bidirectional"))
    )
    (net (code "31") (name "SPI_MISO") (class "Default")
      (node (ref "J12") (pin "2") (pinfunction "2_2") (pintype "passive"))
      (node (ref "J19") (pin "2") (pinfunction "2_2") (pintype "passive"))
      (node (ref "J5") (pin "2") (pinfunction "2_2") (pintype "passive"))
      (node (ref "U1") (pin "29") (pinfunction "P0.15_29") (pintype "bidirectional"))
      (node (ref "U4") (pin "29") (pinfunction "P0.15_29") (pintype "bidirectional"))
      (node (ref "U6") (pin "29") (pinfunction "P0.15_29") (pintype "bidirectional"))
    )
    (net (code "32") (name "SPI_MOSI") (class "Default")
      (node (ref "J12") (pin "4") (pinfunction "4_4") (pintype "passive"))
      (node (ref "J19") (pin "4") (pinfunction "4_4") (pintype "passive"))
      (node (ref "J5") (pin "4") (pinfunction "4_4") (pintype "passive"))
      (node (ref "U1") (pin "27") (pinfunction "P0.13_27") (pintype "bidirectional"))
      (node (ref "U4") (pin "27") (pinfunction "P0.13_27") (pintype "bidirectional"))
      (node (ref "U6") (pin "27") (pinfunction "P0.13_27") (pintype "bidirectional"))
    )
    (net (code "33") (name "SPI_SCK") (class "Default")
      (node (ref "J12") (pin "3") (pinfunction "3_3") (pintype "passive"))
      (node (ref "J19") (pin "3") (pinfunction "3_3") (pintype "passive"))
      (node (ref "J5") (pin "3") (pinfunction "3_3") (pintype "passive"))
      (node (ref "U1") (pin "28") (pinfunction "P0.14_28") (pintype "bidirectional"))
      (node (ref "U4") (pin "28") (pinfunction "P0.14_28") (pintype "bidirectional"))
      (node (ref "U6") (pin "28") (pinfunction "P0.14_28") (pintype "bidirectional"))
    )
    (net (code "34") (name "SPI_SS") (class "Default")
      (node (ref "J12") (pin "1") (pinfunction "1_1") (pintype "passive"))
      (node (ref "J19") (pin "1") (pinfunction "1_1") (pintype "passive"))
      (node (ref "J5") (pin "1") (pinfunction "1_1") (pintype "passive"))
      (node (ref "U1") (pin "30") (pinfunction "P0.16_30") (pintype "bidirectional"))
      (node (ref "U4") (pin "30") (pinfunction "P0.16_30") (pintype "bidirectional"))
      (node (ref "U6") (pin "30") (pinfunction "P0.16_30") (pintype "bidirectional"))
    )
    (net (code "35") (name "SWCLK") (class "Default")
      (node (ref "J11") (pin "2") (pinfunction "2_2") (pintype "passive"))
      (node (ref "J18") (pin "2") (pinfunction "2_2") (pintype "passive"))
      (node (ref "J4") (pin "2") (pinfunction "2_2") (pintype "passive"))
      (node (ref "U1") (pin "36") (pinfunction "SWCLK_36") (pintype "bidirectional"))
      (node (ref "U4") (pin "36") (pinfunction "SWCLK_36") (pintype "bidirectional"))
      (node (ref "U6") (pin "36") (pinfunction "SWCLK_36") (pintype "bidirectional"))
    )
    (net (code "36") (name "SWDIO") (class "Default")
      (node (ref "J11") (pin "3") (pinfunction "3_3") (pintype "passive"))
      (node (ref "J18") (pin "3") (pinfunction "3_3") (pintype "passive"))
      (node (ref "J4") (pin "3") (pinfunction "3_3") (pintype "passive"))
      (node (ref "U1") (pin "37") (pinfunction "SWDIO_37") (pintype "bidirectional"))
      (node (ref "U4") (pin "37") (pinfunction "SWDIO_37") (pintype "bidirectional"))
      (node (ref "U6") (pin "37") (pinfunction "SWDIO_37") (pintype "bidirectional"))
    )
    (net (code "37") (name "TWI_SCL") (class "Default")
      (node (ref "U1") (pin "32") (pinfunction "P0.18_32") (pintype "bidirectional"))
      (node (ref "U2") (pin "23") (pinfunction "SCL/SCLK_23") (pintype "bidirectional"))
      (node (ref "U3") (pin "23") (pinfunction "SCL/SCLK_23") (pintype "bidirectional"))
      (node (ref "U4") (pin "32") (pinfunction "P0.18_32") (pintype "bidirectional"))
      (node (ref "U5") (pin "23") (pinfunction "SCL/SCLK_23") (pintype "bidirectional"))
      (node (ref "U6") (pin "32") (pinfunction "P0.18_32") (pintype "bidirectional"))
    )
    (net (code "38") (name "TWI_SDA") (class "Default")
      (node (ref "U1") (pin "31") (pinfunction "P0.17_31") (pintype "bidirectional"))
      (node (ref "U2") (pin "24") (pinfunction "SDA/SDI_24") (pintype "bidirectional"))
      (node (ref "U3") (pin "24") (pinfunction "SDA/SDI_24") (pintype "bidirectional"))
      (node (ref "U4") (pin "31") (pinfunction "P0.17_31") (pintype "bidirectional"))
      (node (ref "U5") (pin "24") (pinfunction "SDA/SDI_24") (pintype "bidirectional"))
      (node (ref "U6") (pin "31") (pinfunction "P0.17_31") (pintype "bidirectional"))
    )
    (net (code "39") (name "TX") (class "Default")
      (node (ref "J10") (pin "2") (pinfunction "2_2") (pintype "passive"))
      (node (ref "J17") (pin "2") (pinfunction "2_2") (pintype "passive"))
      (node (ref "J3") (pin "2") (pinfunction "2_2") (pintype "passive"))
      (node (ref "U1") (pin "26") (pinfunction "P0.12_26") (pintype "bidirectional"))
      (node (ref "U4") (pin "26") (pinfunction "P0.12_26") (pintype "bidirectional"))
      (node (ref "U6") (pin "26") (pinfunction "P0.12_26") (pintype "bidirectional"))
    )
    (net (code "40") (name "VCC") (class "Default")
      (node (ref "C11") (pin "1") (pinfunction "1_1") (pintype "passive"))
      (node (ref "C3") (pin "1") (pinfunction "1_1") (pintype "passive"))
      (node (ref "C5") (pin "1") (pinfunction "1_1") (pintype "passive"))
      (node (ref "J10") (pin "1") (pinfunction "1_1") (pintype "passive"))
      (node (ref "J11") (pin "1") (pinfunction "1_1") (pintype "passive"))
      (node (ref "J14") (pin "P$1") (pinfunction "1_P$1") (pintype "passive"))
      (node (ref "J17") (pin "1") (pinfunction "1_1") (pintype "passive"))
      (node (ref "J18") (pin "1") (pinfunction "1_1") (pintype "passive"))
      (node (ref "J21") (pin "P$1") (pinfunction "1_P$1") (pintype "passive"))
      (node (ref "J3") (pin "1") (pinfunction "1_1") (pintype "passive"))
      (node (ref "J4") (pin "1") (pinfunction "1_1") (pintype "passive"))
      (node (ref "J7") (pin "P$1") (pinfunction "1_P$1") (pintype "passive"))
      (node (ref "U1") (pin "11") (pinfunction "VDD_11") (pintype "bidirectional"))
      (node (ref "U2") (pin "1") (pinfunction "RESV_1") (pintype "bidirectional"))
      (node (ref "U2") (pin "13") (pinfunction "VDD_13") (pintype "bidirectional"))
      (node (ref "U2") (pin "22") (pinfunction "NCS_22") (pintype "bidirectional"))
      (node (ref "U2") (pin "8") (pinfunction "VDDIO_8") (pintype "bidirectional"))
      (node (ref "U3") (pin "1") (pinfunction "RESV_1") (pintype "bidirectional"))
      (node (ref "U3") (pin "13") (pinfunction "VDD_13") (pintype "bidirectional"))
      (node (ref "U3") (pin "22") (pinfunction "NCS_22") (pintype "bidirectional"))
      (node (ref "U3") (pin "8") (pinfunction "VDDIO_8") (pintype "bidirectional"))
      (node (ref "U4") (pin "11") (pinfunction "VDD_11") (pintype "bidirectional"))
      (node (ref "U5") (pin "1") (pinfunction "RESV_1") (pintype "bidirectional"))
      (node (ref "U5") (pin "13") (pinfunction "VDD_13") (pintype "bidirectional"))
      (node (ref "U5") (pin "22") (pinfunction "NCS_22") (pintype "bidirectional"))
      (node (ref "U5") (pin "8") (pinfunction "VDDIO_8") (pintype "bidirectional"))
      (node (ref "U6") (pin "11") (pinfunction "VDD_11") (pintype "bidirectional"))
    )
    (net (code "41") (name "unconnected-(J22-Pad1)") (class "Default")
      (node (ref "J22") (pin "1") (pinfunction "1_1") (pintype "passive"))
    )
    (net (code "42") (name "unconnected-(J23-Pad1)") (class "Default")
      (node (ref "J23") (pin "1") (pinfunction "1_1") (pintype "passive"))
    )
    (net (code "43") (name "unconnected-(J24-Pad1)") (class "Default")
      (node (ref "J24") (pin "1") (pinfunction "1_1") (pintype "passive"))
    )
    (net (code "44") (name "unconnected-(J25-Pad1)") (class "Default")
      (node (ref "J25") (pin "1") (pinfunction "1_1") (pintype "passive"))
    )
    (net (code "45") (name "unconnected-(J26-Pad1)") (class "Default")
      (node (ref "J26") (pin "1") (pinfunction "1_1") (pintype "passive"))
    )
    (net (code "46") (name "unconnected-(J27-Pad1)") (class "Default")
      (node (ref "J27") (pin "1") (pinfunction "1_1") (pintype "passive"))
    )
    (net (code "47") (name "unconnected-(J28-Pad1)") (class "Default")
      (node (ref "J28") (pin "1") (pinfunction "1_1") (pintype "passive"))
    )
    (net (code "48") (name "unconnected-(J29-Pad1)") (class "Default")
      (node (ref "J29") (pin "1") (pinfunction "1_1") (pintype "passive"))
    )
    (net (code "49") (name "unconnected-(J30-Pad1)") (class "Default")
      (node (ref "J30") (pin "1") (pinfunction "1_1") (pintype "passive"))
    )
    (net (code "50") (name "unconnected-(J31-Pad1)") (class "Default")
      (node (ref "J31") (pin "1") (pinfunction "1_1") (pintype "passive"))
    )
    (net (code "51") (name "unconnected-(J32-Pad1)") (class "Default")
      (node (ref "J32") (pin "1") (pinfunction "1_1") (pintype "passive"))
    )
    (net (code "52") (name "unconnected-(J33-Pad1)") (class "Default")
      (node (ref "J33") (pin "1") (pinfunction "1_1") (pintype "passive"))
    )
    (net (code "53") (name "unconnected-(U1-DCC-Pad10)") (class "Default")
      (node (ref "U1") (pin "10") (pinfunction "DCC_10") (pintype "bidirectional"))
    )
    (net (code "54") (name "unconnected-(U1-DEC4-Pad9)") (class "Default")
      (node (ref "U1") (pin "9") (pinfunction "DEC4_9") (pintype "bidirectional"))
    )
    (net (code "55") (name "unconnected-(U1-P0.22-Pad38)") (class "Default")
      (node (ref "U1") (pin "38") (pinfunction "P0.22_38") (pintype "bidirectional"))
    )
    (net (code "56") (name "unconnected-(U1-P0.23-Pad41)") (class "Default")
      (node (ref "U1") (pin "41") (pinfunction "P0.23_41") (pintype "bidirectional"))
    )
    (net (code "57") (name "unconnected-(U1-P0.24-Pad40)") (class "Default")
      (node (ref "U1") (pin "40") (pinfunction "P0.24_40") (pintype "bidirectional"))
    )
    (net (code "58") (name "unconnected-(U2-AUX_CL-Pad7)") (class "Default")
      (node (ref "U2") (pin "7") (pinfunction "AUX_CL_7") (pintype "bidirectional"))
    )
    (net (code "59") (name "unconnected-(U2-AUX_DA-Pad21)") (class "Default")
      (node (ref "U2") (pin "21") (pinfunction "AUX_DA_21") (pintype "bidirectional"))
    )
    (net (code "60") (name "unconnected-(U2-INT-Pad12)") (class "Default")
      (node (ref "U2") (pin "12") (pinfunction "INT_12") (pintype "bidirectional"))
    )
    (net (code "61") (name "unconnected-(U2-NC1-Pad2)") (class "Default")
      (node (ref "U2") (pin "2") (pinfunction "NC1_2") (pintype "bidirectional"))
    )
    (net (code "62") (name "unconnected-(U2-NC2-Pad3)") (class "Default")
      (node (ref "U2") (pin "3") (pinfunction "NC2_3") (pintype "bidirectional"))
    )
    (net (code "63") (name "unconnected-(U2-NC3-Pad4)") (class "Default")
      (node (ref "U2") (pin "4") (pinfunction "NC3_4") (pintype "bidirectional"))
    )
    (net (code "64") (name "unconnected-(U2-NC4-Pad5)") (class "Default")
      (node (ref "U2") (pin "5") (pinfunction "NC4_5") (pintype "bidirectional"))
    )
    (net (code "65") (name "unconnected-(U2-NC5-Pad6)") (class "Default")
      (node (ref "U2") (pin "6") (pinfunction "NC5_6") (pintype "bidirectional"))
    )
    (net (code "66") (name "unconnected-(U2-NC6-Pad14)") (class "Default")
      (node (ref "U2") (pin "14") (pinfunction "NC6_14") (pintype "bidirectional"))
    )
    (net (code "67") (name "unconnected-(U2-NC7-Pad15)") (class "Default")
      (node (ref "U2") (pin "15") (pinfunction "NC7_15") (pintype "bidirectional"))
    )
    (net (code "68") (name "unconnected-(U2-NC8-Pad16)") (class "Default")
      (node (ref "U2") (pin "16") (pinfunction "NC8_16") (pintype "bidirectional"))
    )
    (net (code "69") (name "unconnected-(U2-NC9-Pad17)") (class "Default")
      (node (ref "U2") (pin "17") (pinfunction "NC9_17") (pintype "bidirectional"))
    )
    (net (code "70") (name "unconnected-(U2-PAD-Pad25)") (class "Default")
      (node (ref "U2") (pin "25") (pinfunction "PAD_25") (pintype "bidirectional"))
    )
    (net (code "71") (name "unconnected-(U2-RESV1-Pad19)") (class "Default")
      (node (ref "U2") (pin "19") (pinfunction "RESV1_19") (pintype "bidirectional"))
    )
    (net (code "72") (name "unconnected-(U3-AUX_CL-Pad7)") (class "Default")
      (node (ref "U3") (pin "7") (pinfunction "AUX_CL_7") (pintype "bidirectional"))
    )
    (net (code "73") (name "unconnected-(U3-AUX_DA-Pad21)") (class "Default")
      (node (ref "U3") (pin "21") (pinfunction "AUX_DA_21") (pintype "bidirectional"))
    )
    (net (code "74") (name "unconnected-(U3-INT-Pad12)") (class "Default")
      (node (ref "U3") (pin "12") (pinfunction "INT_12") (pintype "bidirectional"))
    )
    (net (code "75") (name "unconnected-(U3-NC1-Pad2)") (class "Default")
      (node (ref "U3") (pin "2") (pinfunction "NC1_2") (pintype "bidirectional"))
    )
    (net (code "76") (name "unconnected-(U3-NC2-Pad3)") (class "Default")
      (node (ref "U3") (pin "3") (pinfunction "NC2_3") (pintype "bidirectional"))
    )
    (net (code "77") (name "unconnected-(U3-NC3-Pad4)") (class "Default")
      (node (ref "U3") (pin "4") (pinfunction "NC3_4") (pintype "bidirectional"))
    )
    (net (code "78") (name "unconnected-(U3-NC4-Pad5)") (class "Default")
      (node (ref "U3") (pin "5") (pinfunction "NC4_5") (pintype "bidirectional"))
    )
    (net (code "79") (name "unconnected-(U3-NC5-Pad6)") (class "Default")
      (node (ref "U3") (pin "6") (pinfunction "NC5_6") (pintype "bidirectional"))
    )
    (net (code "80") (name "unconnected-(U3-NC6-Pad14)") (class "Default")
      (node (ref "U3") (pin "14") (pinfunction "NC6_14") (pintype "bidirectional"))
    )
    (net (code "81") (name "unconnected-(U3-NC7-Pad15)") (class "Default")
      (node (ref "U3") (pin "15") (pinfunction "NC7_15") (pintype "bidirectional"))
    )
    (net (code "82") (name "unconnected-(U3-NC8-Pad16)") (class "Default")
      (node (ref "U3") (pin "16") (pinfunction "NC8_16") (pintype "bidirectional"))
    )
    (net (code "83") (name "unconnected-(U3-NC9-Pad17)") (class "Default")
      (node (ref "U3") (pin "17") (pinfunction "NC9_17") (pintype "bidirectional"))
    )
    (net (code "84") (name "unconnected-(U3-PAD-Pad25)") (class "Default")
      (node (ref "U3") (pin "25") (pinfunction "PAD_25") (pintype "bidirectional"))
    )
    (net (code "85") (name "unconnected-(U3-RESV1-Pad19)") (class "Default")
      (node (ref "U3") (pin "19") (pinfunction "RESV1_19") (pintype "bidirectional"))
    )
    (net (code "86") (name "unconnected-(U4-DCC-Pad10)") (class "Default")
      (node (ref "U4") (pin "10") (pinfunction "DCC_10") (pintype "bidirectional"))
    )
    (net (code "87") (name "unconnected-(U4-DEC4-Pad9)") (class "Default")
      (node (ref "U4") (pin "9") (pinfunction "DEC4_9") (pintype "bidirectional"))
    )
    (net (code "88") (name "unconnected-(U4-P0.22-Pad38)") (class "Default")
      (node (ref "U4") (pin "38") (pinfunction "P0.22_38") (pintype "bidirectional"))
    )
    (net (code "89") (name "unconnected-(U4-P0.23-Pad41)") (class "Default")
      (node (ref "U4") (pin "41") (pinfunction "P0.23_41") (pintype "bidirectional"))
    )
    (net (code "90") (name "unconnected-(U4-P0.24-Pad40)") (class "Default")
      (node (ref "U4") (pin "40") (pinfunction "P0.24_40") (pintype "bidirectional"))
    )
    (net (code "91") (name "unconnected-(U5-AUX_CL-Pad7)") (class "Default")
      (node (ref "U5") (pin "7") (pinfunction "AUX_CL_7") (pintype "bidirectional"))
    )
    (net (code "92") (name "unconnected-(U5-AUX_DA-Pad21)") (class "Default")
      (node (ref "U5") (pin "21") (pinfunction "AUX_DA_21") (pintype "bidirectional"))
    )
    (net (code "93") (name "unconnected-(U5-INT-Pad12)") (class "Default")
      (node (ref "U5") (pin "12") (pinfunction "INT_12") (pintype "bidirectional"))
    )
    (net (code "94") (name "unconnected-(U5-NC1-Pad2)") (class "Default")
      (node (ref "U5") (pin "2") (pinfunction "NC1_2") (pintype "bidirectional"))
    )
    (net (code "95") (name "unconnected-(U5-NC2-Pad3)") (class "Default")
      (node (ref "U5") (pin "3") (pinfunction "NC2_3") (pintype "bidirectional"))
    )
    (net (code "96") (name "unconnected-(U5-NC3-Pad4)") (class "Default")
      (node (ref "U5") (pin "4") (pinfunction "NC3_4") (pintype "bidirectional"))
    )
    (net (code "97") (name "unconnected-(U5-NC4-Pad5)") (class "Default")
      (node (ref "U5") (pin "5") (pinfunction "NC4_5") (pintype "bidirectional"))
    )
    (net (code "98") (name "unconnected-(U5-NC5-Pad6)") (class "Default")
      (node (ref "U5") (pin "6") (pinfunction "NC5_6") (pintype "bidirectional"))
    )
    (net (code "99") (name "unconnected-(U5-NC6-Pad14)") (class "Default")
      (node (ref "U5") (pin "14") (pinfunction "NC6_14") (pintype "bidirectional"))
    )
    (net (code "100") (name "unconnected-(U5-NC7-Pad15)") (class "Default")
      (node (ref "U5") (pin "15") (pinfunction "NC7_15") (pintype "bidirectional"))
    )
    (net (code "101") (name "unconnected-(U5-NC8-Pad16)") (class "Default")
      (node (ref "U5") (pin "16") (pinfunction "NC8_16") (pintype "bidirectional"))
    )
    (net (code "102") (name "unconnected-(U5-NC9-Pad17)") (class "Default")
      (node (ref "U5") (pin "17") (pinfunction "NC9_17") (pintype "bidirectional"))
    )
    (net (code "103") (name "unconnected-(U5-PAD-Pad25)") (class "Default")
      (node (ref "U5") (pin "25") (pinfunction "PAD_25") (pintype "bidirectional"))
    )
    (net (code "104") (name "unconnected-(U5-RESV1-Pad19)") (class "Default")
      (node (ref "U5") (pin "19") (pinfunction "RESV1_19") (pintype "bidirectional"))
    )
    (net (code "105") (name "unconnected-(U6-DCC-Pad10)") (class "Default")
      (node (ref "U6") (pin "10") (pinfunction "DCC_10") (pintype "bidirectional"))
    )
    (net (code "106") (name "unconnected-(U6-DEC4-Pad9)") (class "Default")
      (node (ref "U6") (pin "9") (pinfunction "DEC4_9") (pintype "bidirectional"))
    )
    (net (code "107") (name "unconnected-(U6-P0.22-Pad38)") (class "Default")
      (node (ref "U6") (pin "38") (pinfunction "P0.22_38") (pintype "bidirectional"))
    )
    (net (code "108") (name "unconnected-(U6-P0.23-Pad41)") (class "Default")
      (node (ref "U6") (pin "41") (pinfunction "P0.23_41") (pintype "bidirectional"))
    )
    (net (code "109") (name "unconnected-(U6-P0.24-Pad40)") (class "Default")
      (node (ref "U6") (pin "40") (pinfunction "P0.24_40") (pintype "bidirectional"))
    )
  )
)
